# HDMIspartan6_Rev_A_brd.net
KiCad netlist of a schematic drawn in EAGLE
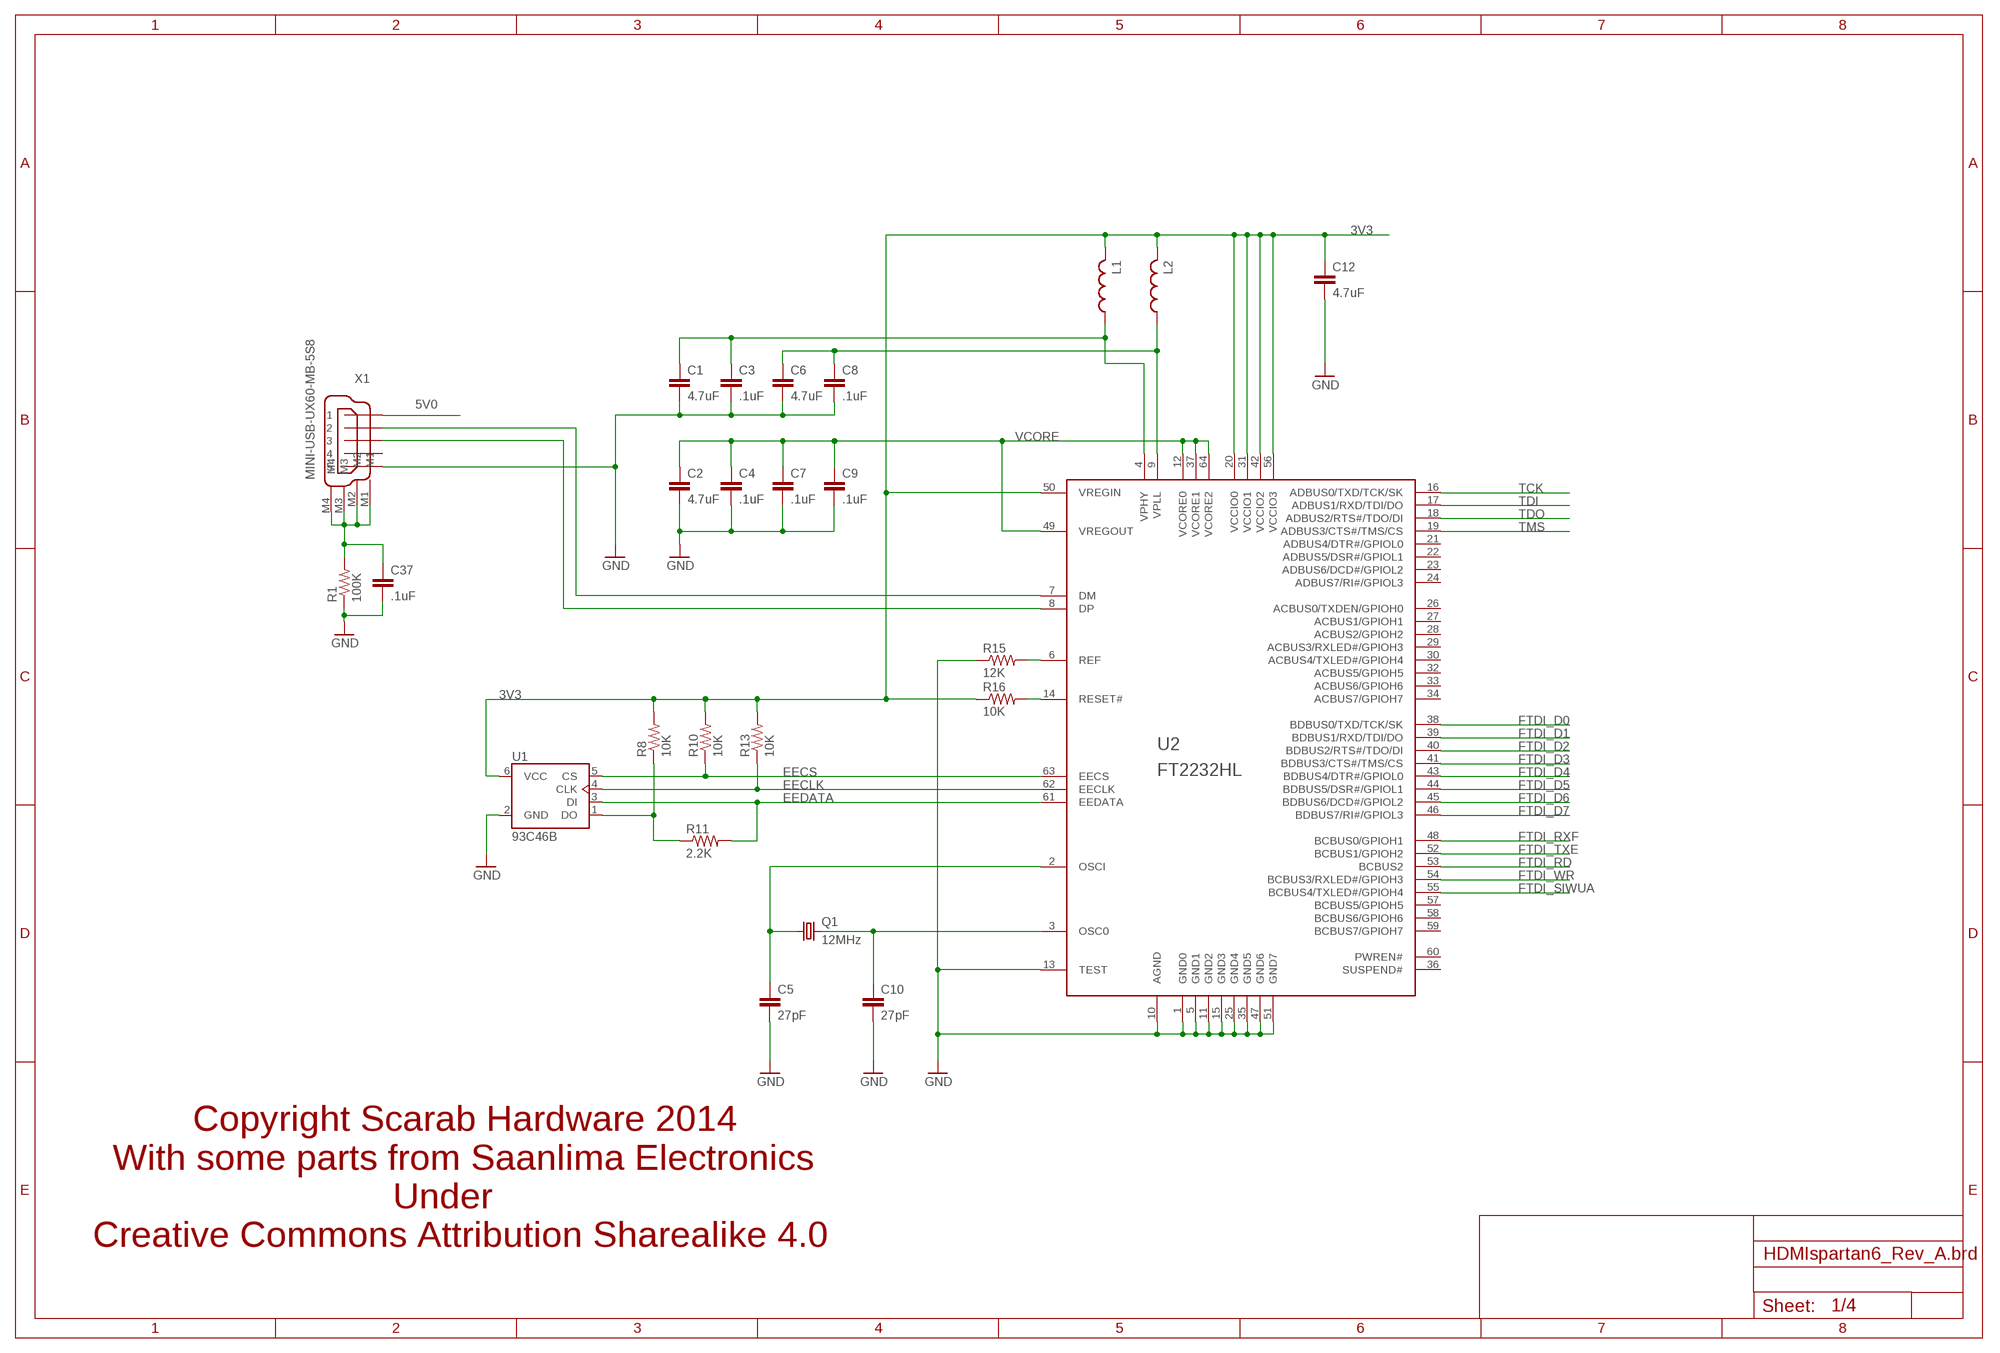
[diagram p0: schematic, sheet 1]
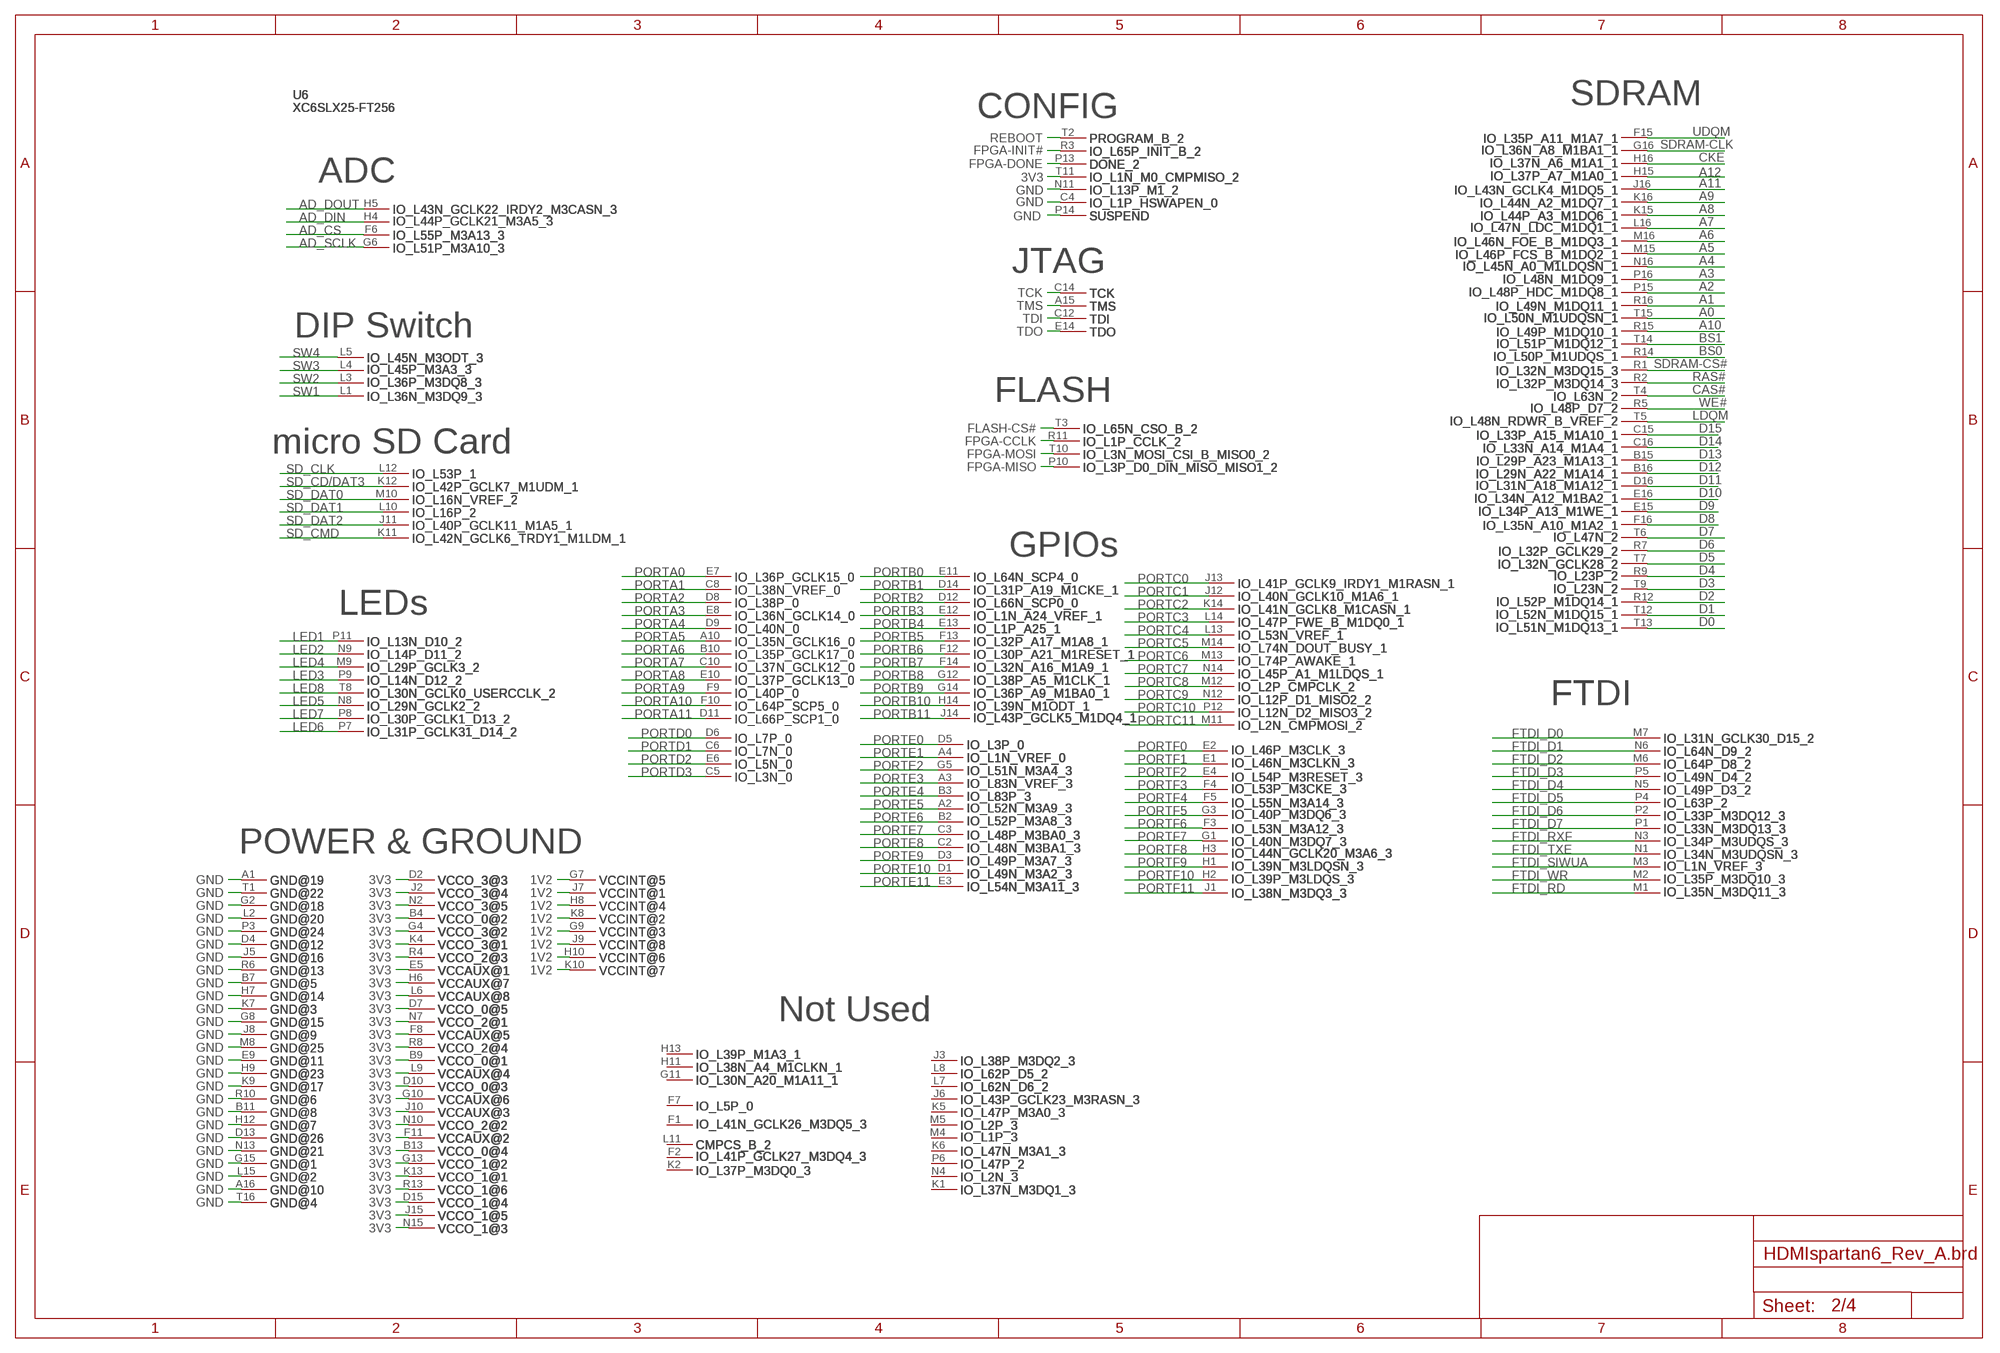
[diagram p1: schematic, sheet 2]
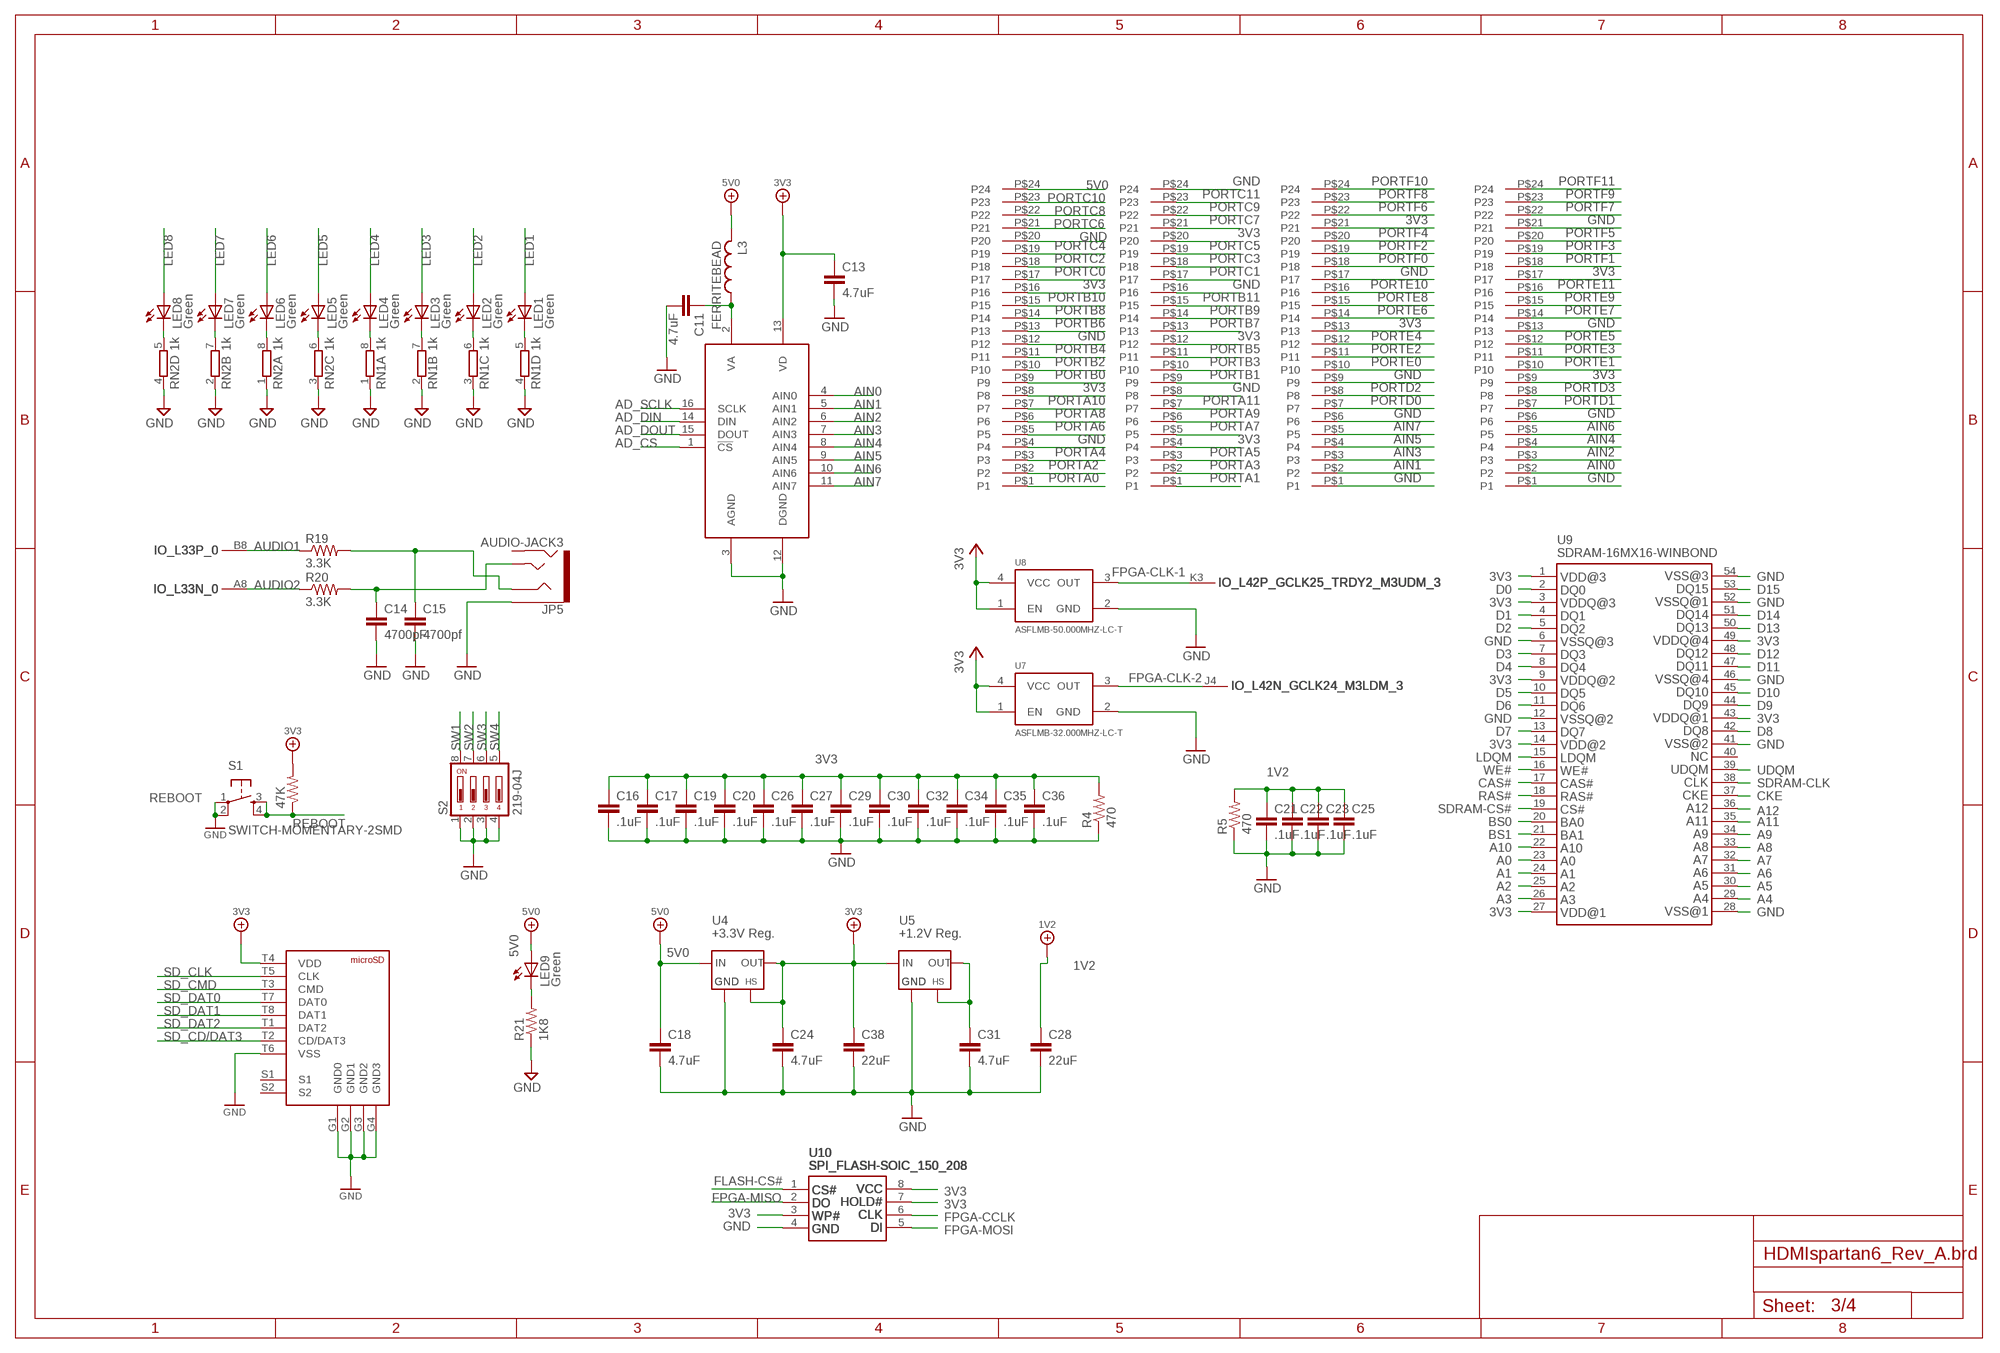
[diagram p2: schematic, sheet 3]
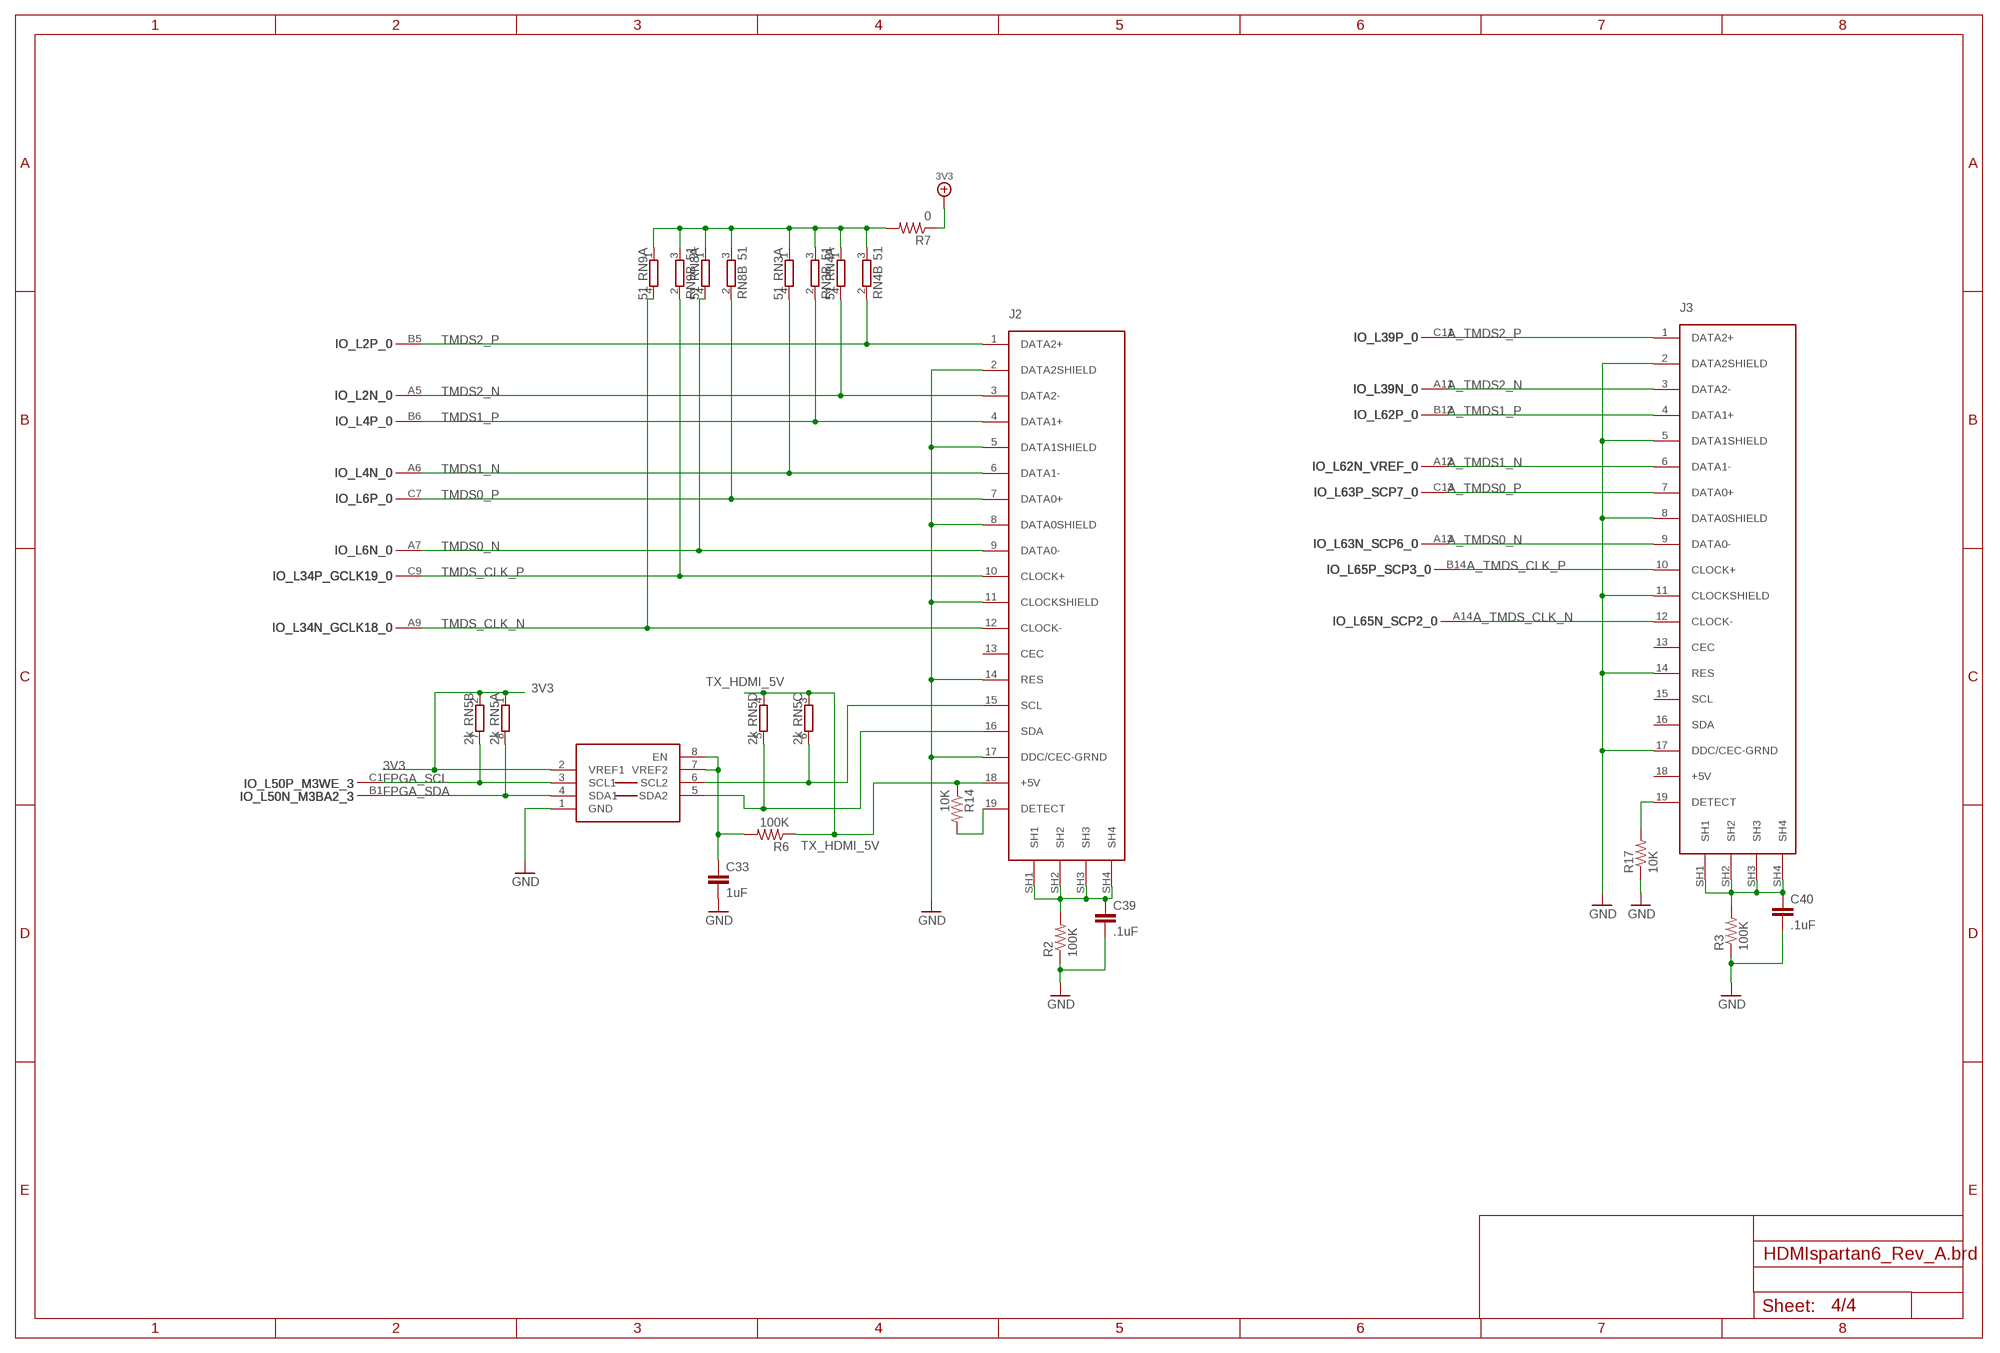
[diagram p3: schematic, sheet 4]

(export (version "E")
  (design (tool "Eeschema 10.0.6"))
  (components
    (comp (ref "U6")
      (value "XC6SLX25-FT256")
      (footprint "eagle-import:XILINX-FT256")
      (fields
        (field (name "DIGIKEY#") "122-1753-ND")
        (field (name "MANF") "XILINX")
        (field (name "MANF#") "XC6SLX25-2FTG256C")
      )
      (libsource (lib "eagle-import") (part "XC6SLX25-FT256"))
    )
    (comp (ref "C11")
      (value "4.7uF")
      (footprint "eagle-import:C0603K")
      (libsource (lib "eagle-import") (part "C-EUC0603K"))
    )
    (comp (ref "C13")
      (value "4.7uF")
      (footprint "eagle-import:C0603K")
      (libsource (lib "eagle-import") (part "C-EUC0603K"))
    )
    (comp (ref "C14")
      (value "4700pF")
      (footprint "eagle-import:C0603K")
      (libsource (lib "eagle-import") (part "C-EUC0603K"))
    )
    (comp (ref "C15")
      (value "4700pf")
      (footprint "eagle-import:C0603K")
      (libsource (lib "eagle-import") (part "C-EUC0603K"))
    )
    (comp (ref "C16")
      (value ".1uF")
      (footprint "eagle-import:C0603K")
      (libsource (lib "eagle-import") (part "C-EUC0603K"))
    )
    (comp (ref "C17")
      (value ".1uF")
      (footprint "eagle-import:C0603K")
      (libsource (lib "eagle-import") (part "C-EUC0603K"))
    )
    (comp (ref "C18")
      (value "4.7uF")
      (footprint "eagle-import:C0603K")
      (fields (field (name "MANF") "Murata"))
      (libsource (lib "eagle-import") (part "C-EUC0603K"))
    )
    (comp (ref "C19")
      (value ".1uF")
      (footprint "eagle-import:C0603K")
      (libsource (lib "eagle-import") (part "C-EUC0603K"))
    )
    (comp (ref "C20")
      (value ".1uF")
      (footprint "eagle-import:C0603K")
      (libsource (lib "eagle-import") (part "C-EUC0603K"))
    )
    (comp (ref "C21")
      (value ".1uF")
      (footprint "eagle-import:C0603K")
      (libsource (lib "eagle-import") (part "C-EUC0603K"))
    )
    (comp (ref "C22")
      (value ".1uF")
      (footprint "eagle-import:C0603K")
      (libsource (lib "eagle-import") (part "C-EUC0603K"))
    )
    (comp (ref "C23")
      (value ".1uF")
      (footprint "eagle-import:C0603K")
      (libsource (lib "eagle-import") (part "C-EUC0603K"))
    )
    (comp (ref "C24")
      (value "4.7uF")
      (footprint "eagle-import:C0603K")
      (fields (field (name "MANF") "Murata"))
      (libsource (lib "eagle-import") (part "C-EUC0603K"))
    )
    (comp (ref "C25")
      (value ".1uF")
      (footprint "eagle-import:C0603K")
      (libsource (lib "eagle-import") (part "C-EUC0603K"))
    )
    (comp (ref "C26")
      (value ".1uF")
      (footprint "eagle-import:C0603K")
      (libsource (lib "eagle-import") (part "C-EUC0603K"))
    )
    (comp (ref "C27")
      (value ".1uF")
      (footprint "eagle-import:C0603K")
      (libsource (lib "eagle-import") (part "C-EUC0603K"))
    )
    (comp (ref "C28")
      (value "22uF")
      (footprint "eagle-import:C0603K")
      (fields (field (name "MANF") "Murata"))
      (libsource (lib "eagle-import") (part "C-EUC0603K"))
    )
    (comp (ref "C29")
      (value ".1uF")
      (footprint "eagle-import:C0603K")
      (libsource (lib "eagle-import") (part "C-EUC0603K"))
    )
    (comp (ref "C30")
      (value ".1uF")
      (footprint "eagle-import:C0603K")
      (libsource (lib "eagle-import") (part "C-EUC0603K"))
    )
    (comp (ref "C31")
      (value "4.7uF")
      (footprint "eagle-import:C0603K")
      (fields (field (name "MANF") "Murata"))
      (libsource (lib "eagle-import") (part "C-EUC0603K"))
    )
    (comp (ref "C32")
      (value ".1uF")
      (footprint "eagle-import:C0603K")
      (libsource (lib "eagle-import") (part "C-EUC0603K"))
    )
    (comp (ref "C34")
      (value ".1uF")
      (footprint "eagle-import:C0603K")
      (libsource (lib "eagle-import") (part "C-EUC0603K"))
    )
    (comp (ref "C35")
      (value ".1uF")
      (footprint "eagle-import:C0603K")
      (libsource (lib "eagle-import") (part "C-EUC0603K"))
    )
    (comp (ref "C36")
      (value ".1uF")
      (footprint "eagle-import:C0603K")
      (libsource (lib "eagle-import") (part "C-EUC0603K"))
    )
    (comp (ref "C38")
      (value "22uF")
      (footprint "eagle-import:C0603K")
      (fields (field (name "MANF") "Murata"))
      (libsource (lib "eagle-import") (part "C-EUC0603K"))
    )
    (comp (ref "J4")
      (value "P24-1")
      (footprint "eagle-import:1X24")
      (libsource (lib "eagle-import") (part "P24-1"))
    )
    (comp (ref "J5")
      (value "MICROSD_MOLEX")
      (footprint "eagle-import:MICROSD_104031")
      (libsource (lib "eagle-import") (part "MICROSD_MOLEX"))
    )
    (comp (ref "J6")
      (value "P24-1")
      (footprint "eagle-import:1X24")
      (libsource (lib "eagle-import") (part "P24-1"))
    )
    (comp (ref "JP5")
      (value "AUDIO-JACK3")
      (footprint "eagle-import:AUDIO-JACK-TRRS-SMD")
      (libsource (lib "eagle-import") (part "AUDIO-JACK3"))
    )
    (comp (ref "L3")
      (value "FERRITEBEAD")
      (footprint "eagle-import:L2012C")
      (libsource (lib "eagle-import") (part "L-USL2012C"))
    )
    (comp (ref "LED1")
      (value "Green")
      (footprint "eagle-import:SML0603")
      (libsource (lib "eagle-import") (part "LEDSML0603"))
    )
    (comp (ref "LED2")
      (value "Green")
      (footprint "eagle-import:SML0603")
      (libsource (lib "eagle-import") (part "LEDSML0603"))
    )
    (comp (ref "LED3")
      (value "Green")
      (footprint "eagle-import:SML0603")
      (libsource (lib "eagle-import") (part "LEDSML0603"))
    )
    (comp (ref "LED4")
      (value "Green")
      (footprint "eagle-import:SML0603")
      (libsource (lib "eagle-import") (part "LEDSML0603"))
    )
    (comp (ref "LED5")
      (value "Green")
      (footprint "eagle-import:SML0603")
      (libsource (lib "eagle-import") (part "LEDSML0603"))
    )
    (comp (ref "LED6")
      (value "Green")
      (footprint "eagle-import:SML0603")
      (libsource (lib "eagle-import") (part "LEDSML0603"))
    )
    (comp (ref "LED7")
      (value "Green")
      (footprint "eagle-import:SML0603")
      (libsource (lib "eagle-import") (part "LEDSML0603"))
    )
    (comp (ref "LED8")
      (value "Green")
      (footprint "eagle-import:SML0603")
      (libsource (lib "eagle-import") (part "LEDSML0603"))
    )
    (comp (ref "LED9")
      (value "Green")
      (footprint "eagle-import:SML0603")
      (libsource (lib "eagle-import") (part "LEDSML0603"))
    )
    (comp (ref "R4")
      (value "470")
      (footprint "eagle-import:R0603")
      (libsource (lib "eagle-import") (part "R-US_R0603"))
    )
    (comp (ref "R5")
      (value "470")
      (footprint "eagle-import:R0603")
      (libsource (lib "eagle-import") (part "R-US_R0603"))
    )
    (comp (ref "R18")
      (value "47K")
      (footprint "eagle-import:R0603")
      (libsource (lib "eagle-import") (part "R-US_R0603"))
    )
    (comp (ref "R19")
      (value "3.3K")
      (footprint "eagle-import:R0603")
      (libsource (lib "eagle-import") (part "R-US_R0603"))
    )
    (comp (ref "R20")
      (value "3.3K")
      (footprint "eagle-import:R0603")
      (libsource (lib "eagle-import") (part "R-US_R0603"))
    )
    (comp (ref "R21")
      (value "1K8")
      (footprint "eagle-import:R0603")
      (libsource (lib "eagle-import") (part "R-US_R0603"))
    )
    (comp (ref "RN1")
      (value "1k")
      (footprint "eagle-import:0603-ARV")
      (libsource (lib "eagle-import") (part "4R-N0603-ARV"))
    )
    (comp (ref "RN2")
      (value "1k")
      (footprint "eagle-import:0603-ARV")
      (libsource (lib "eagle-import") (part "4R-N0603-ARV"))
    )
    (comp (ref "S1")
      (value "SWITCH-MOMENTARY-2SMD")
      (footprint "eagle-import:TACTILE_SWITCH_SMD")
      (libsource (lib "eagle-import") (part "TAC_SWITCHSMD"))
    )
    (comp (ref "S2")
      (value "219-04J")
      (footprint "eagle-import:CTS-219-04J")
      (libsource (lib "eagle-import") (part "219-04J"))
    )
    (comp (ref "U$7")
      (value "P24-1")
      (footprint "eagle-import:1X24")
      (libsource (lib "eagle-import") (part "P24-1"))
    )
    (comp (ref "U$8")
      (value "P24-1")
      (footprint "eagle-import:1X24")
      (libsource (lib "eagle-import") (part "P24-1"))
    )
    (comp (ref "U3")
      (value "ADC088S102CIMT")
      (footprint "eagle-import:TSSOP16")
      (libsource (lib "eagle-import") (part "ADC088S102CIMT"))
    )
    (comp (ref "U4")
      (value "+3.3V Reg.")
      (footprint "eagle-import:SOT223")
      (fields (field (name "MANF") "Diodes/Zetex"))
      (libsource (lib "eagle-import") (part "FAN1117"))
    )
    (comp (ref "U5")
      (value "+1.2V Reg.")
      (footprint "eagle-import:SOT223")
      (fields (field (name "MANF") "Diodes/Zetex"))
      (libsource (lib "eagle-import") (part "FAN1112"))
    )
    (comp (ref "U7")
      (value "ASFLMB-32.000MHZ-LC-T")
      (footprint "eagle-import:CRYSTAL-OSC-SMD-5X3")
      (libsource (lib "eagle-import") (part "OSCILLATOR5X3-PIN1-INDICATED"))
    )
    (comp (ref "U8")
      (value "ASFLMB-50.000MHZ-LC-T")
      (footprint "eagle-import:CRYSTAL-OSC-SMD-5X3")
      (libsource (lib "eagle-import") (part "OSCILLATOR5X3-PIN1-INDICATED"))
    )
    (comp (ref "U9")
      (value "SDRAM-16MX16-WINBOND")
      (footprint "eagle-import:TSOPII-54")
      (fields (field (name "MANF") "Winbond"))
      (libsource (lib "eagle-import") (part "SDRAM-16MX16-WINBOND"))
    )
    (comp (ref "U10")
      (value "SPI_FLASH-SOIC_150_208")
      (footprint "eagle-import:SPI-8_SOIC_150_208")
      (fields
        (field (name "MANF") "Winbond")
        (field (name "DIGIKEY#") "W25Q80BVSNIG-ND")
        (field (name "MANF_1") "Winbond")
        (field (name "MANF#") "W25Q80BVSNIG")
      )
      (libsource (lib "eagle-import") (part "SPI_FLASH-SOIC_150_208"))
    )
    (comp (ref "C33")
      (value "1uF")
      (footprint "eagle-import:C0603K")
      (libsource (lib "eagle-import") (part "C-EUC0603K"))
    )
    (comp (ref "C39")
      (value ".1uF")
      (footprint "eagle-import:C0603K")
      (libsource (lib "eagle-import") (part "C-EUC0603K"))
    )
    (comp (ref "C40")
      (value ".1uF")
      (footprint "eagle-import:C0603K")
      (libsource (lib "eagle-import") (part "C-EUC0603K"))
    )
    (comp (ref "J2")
      (value "HDMI-TYPE-A-RECEPTICALFCI10029449")
      (footprint "eagle-import:FCI-HDMI-TYPE-A-RECEPT")
      (libsource (lib "eagle-import") (part "HDMI-TYPE-A-RECEPTICALFCI10029449"))
    )
    (comp (ref "J3")
      (value "HDMI-TYPE-A-RECEPTICALFCI10029449")
      (footprint "eagle-import:FCI-HDMI-TYPE-A-RECEPT")
      (libsource (lib "eagle-import") (part "HDMI-TYPE-A-RECEPTICALFCI10029449"))
    )
    (comp (ref "R2")
      (value "100K")
      (footprint "eagle-import:R0603")
      (libsource (lib "eagle-import") (part "R-US_R0603"))
    )
    (comp (ref "R3")
      (value "100K")
      (footprint "eagle-import:R0603")
      (libsource (lib "eagle-import") (part "R-US_R0603"))
    )
    (comp (ref "R6")
      (value "100K")
      (footprint "eagle-import:R0603")
      (libsource (lib "eagle-import") (part "R-US_R0603"))
    )
    (comp (ref "R7")
      (value "0")
      (footprint "eagle-import:R0603")
      (libsource (lib "eagle-import") (part "R-US_R0603"))
    )
    (comp (ref "R14")
      (value "10K")
      (footprint "eagle-import:R0603")
      (libsource (lib "eagle-import") (part "R-US_R0603"))
    )
    (comp (ref "R17")
      (value "10K")
      (footprint "eagle-import:R0603")
      (libsource (lib "eagle-import") (part "R-US_R0603"))
    )
    (comp (ref "RN3")
      (value "51")
      (footprint "eagle-import:EXB34V")
      (libsource (lib "eagle-import") (part "2R-NEXB34V"))
    )
    (comp (ref "RN4")
      (value "51")
      (footprint "eagle-import:EXB34V")
      (libsource (lib "eagle-import") (part "2R-NEXB34V"))
    )
    (comp (ref "RN5")
      (value "2k")
      (footprint "eagle-import:0603-ARV")
      (libsource (lib "eagle-import") (part "4R-N0603-ARV"))
    )
    (comp (ref "RN8")
      (value "51")
      (footprint "eagle-import:EXB34V")
      (libsource (lib "eagle-import") (part "2R-NEXB34V"))
    )
    (comp (ref "RN9")
      (value "51")
      (footprint "eagle-import:EXB34V")
      (libsource (lib "eagle-import") (part "2R-NEXB34V"))
    )
    (comp (ref "U11")
      (value "PCA9306")
      (footprint "eagle-import:PSOP-8")
      (libsource (lib "eagle-import") (part "PCA9306"))
    )
    (comp (ref "C1")
      (value "4.7uF")
      (footprint "eagle-import:C0603K")
      (libsource (lib "eagle-import") (part "C-EUC0603K"))
    )
    (comp (ref "C2")
      (value "4.7uF")
      (footprint "eagle-import:C0603K")
      (libsource (lib "eagle-import") (part "C-EUC0603K"))
    )
    (comp (ref "C3")
      (value ".1uF")
      (footprint "eagle-import:C0603K")
      (libsource (lib "eagle-import") (part "C-EUC0603K"))
    )
    (comp (ref "C4")
      (value ".1uF")
      (footprint "eagle-import:C0603K")
      (libsource (lib "eagle-import") (part "C-EUC0603K"))
    )
    (comp (ref "C5")
      (value "27pF")
      (footprint "eagle-import:C0603K")
      (libsource (lib "eagle-import") (part "C-EUC0603K"))
    )
    (comp (ref "C6")
      (value "4.7uF")
      (footprint "eagle-import:C0603K")
      (libsource (lib "eagle-import") (part "C-EUC0603K"))
    )
    (comp (ref "C7")
      (value ".1uF")
      (footprint "eagle-import:C0603K")
      (libsource (lib "eagle-import") (part "C-EUC0603K"))
    )
    (comp (ref "C8")
      (value ".1uF")
      (footprint "eagle-import:C0603K")
      (libsource (lib "eagle-import") (part "C-EUC0603K"))
    )
    (comp (ref "C9")
      (value ".1uF")
      (footprint "eagle-import:C0603K")
      (libsource (lib "eagle-import") (part "C-EUC0603K"))
    )
    (comp (ref "C10")
      (value "27pF")
      (footprint "eagle-import:C0603K")
      (libsource (lib "eagle-import") (part "C-EUC0603K"))
    )
    (comp (ref "C12")
      (value "4.7uF")
      (footprint "eagle-import:C0603K")
      (libsource (lib "eagle-import") (part "C-EUC0603K"))
    )
    (comp (ref "C37")
      (value ".1uF")
      (footprint "eagle-import:C0603K")
      (libsource (lib "eagle-import") (part "C-EUC0603K"))
    )
    (comp (ref "L1")
      (value "L-USL2012C")
      (footprint "eagle-import:L2012C")
      (libsource (lib "eagle-import") (part "L-USL2012C"))
    )
    (comp (ref "L2")
      (value "L-USL2012C")
      (footprint "eagle-import:L2012C")
      (libsource (lib "eagle-import") (part "L-USL2012C"))
    )
    (comp (ref "Q1")
      (value "12MHz")
      (footprint "eagle-import:CRYSTAL3.2X2.5MM")
      (libsource (lib "eagle-import") (part "CRYSTAL3.2X2.5"))
    )
    (comp (ref "R1")
      (value "100K")
      (footprint "eagle-import:R0603")
      (libsource (lib "eagle-import") (part "R-US_R0603"))
    )
    (comp (ref "R8")
      (value "10K")
      (footprint "eagle-import:R0603")
      (libsource (lib "eagle-import") (part "R-US_R0603"))
    )
    (comp (ref "R10")
      (value "10K")
      (footprint "eagle-import:R0603")
      (libsource (lib "eagle-import") (part "R-US_R0603"))
    )
    (comp (ref "R11")
      (value "2.2K")
      (footprint "eagle-import:R0603")
      (libsource (lib "eagle-import") (part "R-US_R0603"))
    )
    (comp (ref "R13")
      (value "10K")
      (footprint "eagle-import:R0603")
      (libsource (lib "eagle-import") (part "R-US_R0603"))
    )
    (comp (ref "R15")
      (value "12K")
      (footprint "eagle-import:R0603")
      (libsource (lib "eagle-import") (part "R-US_R0603"))
    )
    (comp (ref "R16")
      (value "10K")
      (footprint "eagle-import:R0603")
      (libsource (lib "eagle-import") (part "R-US_R0603"))
    )
    (comp (ref "U1")
      (value "93C46B")
      (footprint "eagle-import:SOT23-6")
      (libsource (lib "eagle-import") (part "DIGITAL-EEPROM-MICROWIRE-6P_SOT23"))
    )
    (comp (ref "U2")
      (value "FT2232HL")
      (footprint "eagle-import:LQFP64")
      (libsource (lib "eagle-import") (part "FT2232H"))
    )
    (comp (ref "X1")
      (value "MINI-USB-UX60-MB-5S8")
      (footprint "eagle-import:UX60-MB-5S8")
      (libsource (lib "eagle-import") (part "MINI-USB-UX60-MB-5S8"))
    )
  )
  (nets
    (net (code "1") (name "1V2") (class "Default")
      (node (ref "C21") (pin "1") (pinfunction "1_1") (pintype "passive"))
      (node (ref "C22") (pin "1") (pinfunction "1_1") (pintype "passive"))
      (node (ref "C23") (pin "1") (pinfunction "1_1") (pintype "passive"))
      (node (ref "C25") (pin "1") (pinfunction "1_1") (pintype "passive"))
      (node (ref "C28") (pin "1") (pinfunction "1_1") (pintype "passive"))
      (node (ref "R5") (pin "2") (pinfunction "2_2") (pintype "passive"))
      (node (ref "U6") (pin "G7") (pinfunction "1_G7") (pintype "input"))
      (node (ref "U6") (pin "G9") (pinfunction "1_G9") (pintype "input"))
      (node (ref "U6") (pin "H10") (pinfunction "1_H10") (pintype "input"))
      (node (ref "U6") (pin "H8") (pinfunction "1_H8") (pintype "input"))
      (node (ref "U6") (pin "J7") (pinfunction "1_J7") (pintype "input"))
      (node (ref "U6") (pin "J9") (pinfunction "1_J9") (pintype "input"))
      (node (ref "U6") (pin "K10") (pinfunction "1_K10") (pintype "input"))
      (node (ref "U6") (pin "K8") (pinfunction "1_K8") (pintype "input"))
    )
    (net (code "2") (name "3V3") (class "Default")
      (node (ref "C12") (pin "1") (pinfunction "1_1") (pintype "passive"))
      (node (ref "C13") (pin "1") (pinfunction "1_1") (pintype "passive"))
      (node (ref "C16") (pin "1") (pinfunction "1_1") (pintype "passive"))
      (node (ref "C17") (pin "1") (pinfunction "1_1") (pintype "passive"))
      (node (ref "C19") (pin "1") (pinfunction "1_1") (pintype "passive"))
      (node (ref "C20") (pin "1") (pinfunction "1_1") (pintype "passive"))
      (node (ref "C24") (pin "1") (pinfunction "1_1") (pintype "passive"))
      (node (ref "C26") (pin "1") (pinfunction "1_1") (pintype "passive"))
      (node (ref "C27") (pin "1") (pinfunction "1_1") (pintype "passive"))
      (node (ref "C29") (pin "1") (pinfunction "1_1") (pintype "passive"))
      (node (ref "C30") (pin "1") (pinfunction "1_1") (pintype "passive"))
      (node (ref "C32") (pin "1") (pinfunction "1_1") (pintype "passive"))
      (node (ref "C34") (pin "1") (pinfunction "1_1") (pintype "passive"))
      (node (ref "C35") (pin "1") (pinfunction "1_1") (pintype "passive"))
      (node (ref "C36") (pin "1") (pinfunction "1_1") (pintype "passive"))
      (node (ref "C38") (pin "1") (pinfunction "1_1") (pintype "passive"))
      (node (ref "J4") (pin "P$13") (pinfunction "P13_P$13") (pintype "bidirectional"))
      (node (ref "J4") (pin "P$21") (pinfunction "P21_P$21") (pintype "bidirectional"))
      (node (ref "J5") (pin "T4") (pinfunction "VDD_T4") (pintype "bidirectional"))
      (node (ref "J6") (pin "P$17") (pinfunction "P17_P$17") (pintype "bidirectional"))
      (node (ref "J6") (pin "P$9") (pinfunction "P9_P$9") (pintype "bidirectional"))
      (node (ref "L1") (pin "2") (pinfunction "2_2") (pintype "passive"))
      (node (ref "L2") (pin "2") (pinfunction "2_2") (pintype "passive"))
      (node (ref "R10") (pin "2") (pinfunction "2_2") (pintype "passive"))
      (node (ref "R13") (pin "2") (pinfunction "2_2") (pintype "passive"))
      (node (ref "R16") (pin "1") (pinfunction "1_1") (pintype "passive"))
      (node (ref "R18") (pin "2") (pinfunction "2_2") (pintype "passive"))
      (node (ref "R4") (pin "2") (pinfunction "2_2") (pintype "passive"))
      (node (ref "R7") (pin "1") (pinfunction "1_1") (pintype "passive"))
      (node (ref "R8") (pin "2") (pinfunction "2_2") (pintype "passive"))
      (node (ref "RN5") (pin "1") (pinfunction "1_1") (pintype "passive"))
      (node (ref "RN5") (pin "2") (pinfunction "1_2") (pintype "passive"))
      (node (ref "U$7") (pin "P$16") (pinfunction "P16_P$16") (pintype "bidirectional"))
      (node (ref "U$7") (pin "P$8") (pinfunction "P8_P$8") (pintype "bidirectional"))
      (node (ref "U$8") (pin "P$12") (pinfunction "P12_P$12") (pintype "bidirectional"))
      (node (ref "U$8") (pin "P$20") (pinfunction "P20_P$20") (pintype "bidirectional"))
      (node (ref "U$8") (pin "P$4") (pinfunction "P4_P$4") (pintype "bidirectional"))
      (node (ref "U1") (pin "6") (pinfunction "VCC_6") (pintype "input"))
      (node (ref "U10") (pin "3") (pinfunction "1_3") (pintype "input"))
      (node (ref "U10") (pin "7") (pinfunction "1_7") (pintype "input"))
      (node (ref "U10") (pin "8") (pinfunction "1_8") (pintype "input"))
      (node (ref "U11") (pin "2") (pinfunction "VREF1_2") (pintype "bidirectional"))
      (node (ref "U2") (pin "20") (pinfunction "VCCIO0_20") (pintype "bidirectional"))
      (node (ref "U2") (pin "31") (pinfunction "VCCIO1_31") (pintype "bidirectional"))
      (node (ref "U2") (pin "42") (pinfunction "VCCIO2_42") (pintype "bidirectional"))
      (node (ref "U2") (pin "50") (pinfunction "VREGIN_50") (pintype "bidirectional"))
      (node (ref "U2") (pin "56") (pinfunction "VCCIO3_56") (pintype "bidirectional"))
      (node (ref "U3") (pin "13") (pinfunction "VD_13") (pintype "power_in"))
      (node (ref "U4") (pin "2") (pinfunction "OUT_2") (pintype "passive"))
      (node (ref "U4") (pin "4") (pinfunction "HS_4") (pintype "passive"))
      (node (ref "U5") (pin "3") (pinfunction "IN_3") (pintype "input"))
      (node (ref "U6") (pin "B13") (pinfunction "1_B13") (pintype "input"))
      (node (ref "U6") (pin "B4") (pinfunction "1_B4") (pintype "input"))
      (node (ref "U6") (pin "B9") (pinfunction "1_B9") (pintype "input"))
      (node (ref "U6") (pin "D10") (pinfunction "1_D10") (pintype "input"))
      (node (ref "U6") (pin "D15") (pinfunction "1_D15") (pintype "input"))
      (node (ref "U6") (pin "D2") (pinfunction "1_D2") (pintype "input"))
      (node (ref "U6") (pin "D7") (pinfunction "1_D7") (pintype "input"))
      (node (ref "U6") (pin "E5") (pinfunction "1_E5") (pintype "input"))
      (node (ref "U6") (pin "F11") (pinfunction "1_F11") (pintype "input"))
      (node (ref "U6") (pin "F8") (pinfunction "1_F8") (pintype "input"))
      (node (ref "U6") (pin "G10") (pinfunction "1_G10") (pintype "input"))
      (node (ref "U6") (pin "G13") (pinfunction "1_G13") (pintype "input"))
      (node (ref "U6") (pin "G4") (pinfunction "1_G4") (pintype "input"))
      (node (ref "U6") (pin "H6") (pinfunction "1_H6") (pintype "input"))
      (node (ref "U6") (pin "J10") (pinfunction "1_J10") (pintype "input"))
      (node (ref "U6") (pin "J15") (pinfunction "1_J15") (pintype "input"))
      (node (ref "U6") (pin "J2") (pinfunction "1_J2") (pintype "input"))
      (node (ref "U6") (pin "K13") (pinfunction "1_K13") (pintype "input"))
      (node (ref "U6") (pin "K4") (pinfunction "1_K4") (pintype "input"))
      (node (ref "U6") (pin "L6") (pinfunction "1_L6") (pintype "input"))
      (node (ref "U6") (pin "L9") (pinfunction "1_L9") (pintype "input"))
      (node (ref "U6") (pin "N10") (pinfunction "1_N10") (pintype "input"))
      (node (ref "U6") (pin "N15") (pinfunction "1_N15") (pintype "input"))
      (node (ref "U6") (pin "N2") (pinfunction "1_N2") (pintype "input"))
      (node (ref "U6") (pin "N7") (pinfunction "1_N7") (pintype "input"))
      (node (ref "U6") (pin "R13") (pinfunction "1_R13") (pintype "input"))
      (node (ref "U6") (pin "R4") (pinfunction "1_R4") (pintype "input"))
      (node (ref "U6") (pin "R8") (pinfunction "1_R8") (pintype "input"))
      (node (ref "U6") (pin "T11") (pinfunction "1_T11") (pintype "bidirectional"))
      (node (ref "U7") (pin "1") (pinfunction "EN_1") (pintype "bidirectional"))
      (node (ref "U7") (pin "4") (pinfunction "VCC_4") (pintype "bidirectional"))
      (node (ref "U8") (pin "1") (pinfunction "EN_1") (pintype "bidirectional"))
      (node (ref "U8") (pin "4") (pinfunction "VCC_4") (pintype "bidirectional"))
      (node (ref "U9") (pin "1") (pinfunction "P$1_1") (pintype "bidirectional"))
      (node (ref "U9") (pin "14") (pinfunction "P$1_14") (pintype "bidirectional"))
      (node (ref "U9") (pin "27") (pinfunction "P$1_27") (pintype "bidirectional"))
      (node (ref "U9") (pin "3") (pinfunction "P$1_3") (pintype "bidirectional"))
      (node (ref "U9") (pin "43") (pinfunction "P$1_43") (pintype "bidirectional"))
      (node (ref "U9") (pin "49") (pinfunction "P$1_49") (pintype "bidirectional"))
      (node (ref "U9") (pin "9") (pinfunction "P$1_9") (pintype "bidirectional"))
    )
    (net (code "3") (name "5V0") (class "Default")
      (node (ref "C18") (pin "1") (pinfunction "1_1") (pintype "passive"))
      (node (ref "L3") (pin "2") (pinfunction "2_2") (pintype "passive"))
      (node (ref "LED9") (pin "A") (pinfunction "A_A") (pintype "passive"))
      (node (ref "U$7") (pin "P$24") (pinfunction "P24_P$24") (pintype "bidirectional"))
      (node (ref "U4") (pin "3") (pinfunction "IN_3") (pintype "input"))
      (node (ref "X1") (pin "1") (pinfunction "1_1") (pintype "input"))
    )
    (net (code "4") (name "A0") (class "Default")
      (node (ref "U6") (pin "T15") (pinfunction "1_T15") (pintype "bidirectional"))
      (node (ref "U9") (pin "23") (pinfunction "P$1_23") (pintype "bidirectional"))
    )
    (net (code "5") (name "A1") (class "Default")
      (node (ref "U6") (pin "R16") (pinfunction "1_R16") (pintype "bidirectional"))
      (node (ref "U9") (pin "24") (pinfunction "P$1_24") (pintype "bidirectional"))
    )
    (net (code "6") (name "A2") (class "Default")
      (node (ref "U6") (pin "P15") (pinfunction "1_P15") (pintype "bidirectional"))
      (node (ref "U9") (pin "25") (pinfunction "P$1_25") (pintype "bidirectional"))
    )
    (net (code "7") (name "A3") (class "Default")
      (node (ref "U6") (pin "P16") (pinfunction "1_P16") (pintype "bidirectional"))
      (node (ref "U9") (pin "26") (pinfunction "P$1_26") (pintype "bidirectional"))
    )
    (net (code "8") (name "A4") (class "Default")
      (node (ref "U6") (pin "N16") (pinfunction "1_N16") (pintype "bidirectional"))
      (node (ref "U9") (pin "29") (pinfunction "P$1_29") (pintype "bidirectional"))
    )
    (net (code "9") (name "A5") (class "Default")
      (node (ref "U6") (pin "M15") (pinfunction "1_M15") (pintype "bidirectional"))
      (node (ref "U9") (pin "30") (pinfunction "P$1_30") (pintype "bidirectional"))
    )
    (net (code "10") (name "A6") (class "Default")
      (node (ref "U6") (pin "M16") (pinfunction "1_M16") (pintype "bidirectional"))
      (node (ref "U9") (pin "31") (pinfunction "P$1_31") (pintype "bidirectional"))
    )
    (net (code "11") (name "A7") (class "Default")
      (node (ref "U6") (pin "L16") (pinfunction "1_L16") (pintype "bidirectional"))
      (node (ref "U9") (pin "32") (pinfunction "P$1_32") (pintype "bidirectional"))
    )
    (net (code "12") (name "A8") (class "Default")
      (node (ref "U6") (pin "K15") (pinfunction "1_K15") (pintype "bidirectional"))
      (node (ref "U9") (pin "33") (pinfunction "P$1_33") (pintype "bidirectional"))
    )
    (net (code "13") (name "A9") (class "Default")
      (node (ref "U6") (pin "K16") (pinfunction "1_K16") (pintype "bidirectional"))
      (node (ref "U9") (pin "34") (pinfunction "P$1_34") (pintype "bidirectional"))
    )
    (net (code "14") (name "A10") (class "Default")
      (node (ref "U6") (pin "R15") (pinfunction "1_R15") (pintype "bidirectional"))
      (node (ref "U9") (pin "22") (pinfunction "P$1_22") (pintype "bidirectional"))
    )
    (net (code "15") (name "A11") (class "Default")
      (node (ref "U6") (pin "J16") (pinfunction "1_J16") (pintype "bidirectional"))
      (node (ref "U9") (pin "35") (pinfunction "P$1_35") (pintype "bidirectional"))
    )
    (net (code "16") (name "A12") (class "Default")
      (node (ref "U6") (pin "H15") (pinfunction "1_H15") (pintype "bidirectional"))
      (node (ref "U9") (pin "36") (pinfunction "P$1_36") (pintype "bidirectional"))
    )
    (net (code "17") (name "AD_CS") (class "Default")
      (node (ref "U3") (pin "1") (pinfunction "~{CS}_1") (pintype "input"))
      (node (ref "U6") (pin "F6") (pinfunction "1_F6") (pintype "bidirectional"))
    )
    (net (code "18") (name "AD_DIN") (class "Default")
      (node (ref "U3") (pin "14") (pinfunction "DIN_14") (pintype "input"))
      (node (ref "U6") (pin "H4") (pinfunction "1_H4") (pintype "bidirectional"))
    )
    (net (code "19") (name "AD_DOUT") (class "Default")
      (node (ref "U3") (pin "15") (pinfunction "DOUT_15") (pintype "output"))
      (node (ref "U6") (pin "H5") (pinfunction "1_H5") (pintype "bidirectional"))
    )
    (net (code "20") (name "AD_SCLK") (class "Default")
      (node (ref "U3") (pin "16") (pinfunction "SCLK_16") (pintype "input"))
      (node (ref "U6") (pin "G6") (pinfunction "1_G6") (pintype "bidirectional"))
    )
    (net (code "21") (name "AIN0") (class "Default")
      (node (ref "J6") (pin "P$2") (pinfunction "P2_P$2") (pintype "bidirectional"))
      (node (ref "U3") (pin "4") (pinfunction "AIN0_4") (pintype "input"))
    )
    (net (code "22") (name "AIN1") (class "Default")
      (node (ref "J4") (pin "P$2") (pinfunction "P2_P$2") (pintype "bidirectional"))
      (node (ref "U3") (pin "5") (pinfunction "AIN1_5") (pintype "input"))
    )
    (net (code "23") (name "AIN2") (class "Default")
      (node (ref "J6") (pin "P$3") (pinfunction "P3_P$3") (pintype "bidirectional"))
      (node (ref "U3") (pin "6") (pinfunction "AIN2_6") (pintype "input"))
    )
    (net (code "24") (name "AIN3") (class "Default")
      (node (ref "J4") (pin "P$3") (pinfunction "P3_P$3") (pintype "bidirectional"))
      (node (ref "U3") (pin "7") (pinfunction "AIN3_7") (pintype "input"))
    )
    (net (code "25") (name "AIN4") (class "Default")
      (node (ref "J6") (pin "P$4") (pinfunction "P4_P$4") (pintype "bidirectional"))
      (node (ref "U3") (pin "8") (pinfunction "AIN4_8") (pintype "input"))
    )
    (net (code "26") (name "AIN5") (class "Default")
      (node (ref "J4") (pin "P$4") (pinfunction "P4_P$4") (pintype "bidirectional"))
      (node (ref "U3") (pin "9") (pinfunction "AIN5_9") (pintype "input"))
    )
    (net (code "27") (name "AIN6") (class "Default")
      (node (ref "J6") (pin "P$5") (pinfunction "P5_P$5") (pintype "bidirectional"))
      (node (ref "U3") (pin "10") (pinfunction "AIN6_10") (pintype "input"))
    )
    (net (code "28") (name "AIN7") (class "Default")
      (node (ref "J4") (pin "P$5") (pinfunction "P5_P$5") (pintype "bidirectional"))
      (node (ref "U3") (pin "11") (pinfunction "AIN7_11") (pintype "input"))
    )
    (net (code "29") (name "AUDIO1") (class "Default")
      (node (ref "R19") (pin "1") (pinfunction "1_1") (pintype "passive"))
      (node (ref "U6") (pin "B8") (pinfunction "1_B8") (pintype "bidirectional"))
    )
    (net (code "30") (name "AUDIO2") (class "Default")
      (node (ref "R20") (pin "1") (pinfunction "1_1") (pintype "passive"))
      (node (ref "U6") (pin "A8") (pinfunction "1_A8") (pintype "bidirectional"))
    )
    (net (code "31") (name "A_TMDS0_N") (class "Default")
      (node (ref "J3") (pin "9") (pinfunction "DATA0-_9") (pintype "bidirectional"))
      (node (ref "U6") (pin "A13") (pinfunction "1_A13") (pintype "bidirectional"))
    )
    (net (code "32") (name "A_TMDS0_P") (class "Default")
      (node (ref "J3") (pin "7") (pinfunction "DATA0+_7") (pintype "bidirectional"))
      (node (ref "U6") (pin "C13") (pinfunction "1_C13") (pintype "bidirectional"))
    )
    (net (code "33") (name "A_TMDS1_N") (class "Default")
      (node (ref "J3") (pin "6") (pinfunction "DATA1-_6") (pintype "bidirectional"))
      (node (ref "U6") (pin "A12") (pinfunction "1_A12") (pintype "bidirectional"))
    )
    (net (code "34") (name "A_TMDS1_P") (class "Default")
      (node (ref "J3") (pin "4") (pinfunction "DATA1+_4") (pintype "bidirectional"))
      (node (ref "U6") (pin "B12") (pinfunction "1_B12") (pintype "bidirectional"))
    )
    (net (code "35") (name "A_TMDS2_N") (class "Default")
      (node (ref "J3") (pin "3") (pinfunction "DATA2-_3") (pintype "bidirectional"))
      (node (ref "U6") (pin "A11") (pinfunction "1_A11") (pintype "bidirectional"))
    )
    (net (code "36") (name "A_TMDS2_P") (class "Default")
      (node (ref "J3") (pin "1") (pinfunction "DATA2+_1") (pintype "bidirectional"))
      (node (ref "U6") (pin "C11") (pinfunction "1_C11") (pintype "bidirectional"))
    )
    (net (code "37") (name "A_TMDS_CLK_N") (class "Default")
      (node (ref "J3") (pin "12") (pinfunction "CLOCK-_12") (pintype "bidirectional"))
      (node (ref "U6") (pin "A14") (pinfunction "1_A14") (pintype "bidirectional"))
    )
    (net (code "38") (name "A_TMDS_CLK_P") (class "Default")
      (node (ref "J3") (pin "10") (pinfunction "CLOCK+_10") (pintype "bidirectional"))
      (node (ref "U6") (pin "B14") (pinfunction "1_B14") (pintype "bidirectional"))
    )
    (net (code "39") (name "BS0") (class "Default")
      (node (ref "U6") (pin "R14") (pinfunction "1_R14") (pintype "bidirectional"))
      (node (ref "U9") (pin "20") (pinfunction "P$1_20") (pintype "bidirectional"))
    )
    (net (code "40") (name "BS1") (class "Default")
      (node (ref "U6") (pin "T14") (pinfunction "1_T14") (pintype "bidirectional"))
      (node (ref "U9") (pin "21") (pinfunction "P$1_21") (pintype "bidirectional"))
    )
    (net (code "41") (name "CAS#") (class "Default")
      (node (ref "U6") (pin "T4") (pinfunction "1_T4") (pintype "bidirectional"))
      (node (ref "U9") (pin "17") (pinfunction "P$1_17") (pintype "bidirectional"))
    )
    (net (code "42") (name "CKE") (class "Default")
      (node (ref "U6") (pin "H16") (pinfunction "1_H16") (pintype "bidirectional"))
      (node (ref "U9") (pin "37") (pinfunction "P$1_37") (pintype "bidirectional"))
    )
    (net (code "43") (name "D0") (class "Default")
      (node (ref "U6") (pin "T13") (pinfunction "1_T13") (pintype "bidirectional"))
      (node (ref "U9") (pin "2") (pinfunction "P$1_2") (pintype "bidirectional"))
    )
    (net (code "44") (name "D1") (class "Default")
      (node (ref "U6") (pin "T12") (pinfunction "1_T12") (pintype "bidirectional"))
      (node (ref "U9") (pin "4") (pinfunction "P$1_4") (pintype "bidirectional"))
    )
    (net (code "45") (name "D2") (class "Default")
      (node (ref "U6") (pin "R12") (pinfunction "1_R12") (pintype "bidirectional"))
      (node (ref "U9") (pin "5") (pinfunction "P$1_5") (pintype "bidirectional"))
    )
    (net (code "46") (name "D3") (class "Default")
      (node (ref "U6") (pin "T9") (pinfunction "1_T9") (pintype "bidirectional"))
      (node (ref "U9") (pin "7") (pinfunction "P$1_7") (pintype "bidirectional"))
    )
    (net (code "47") (name "D4") (class "Default")
      (node (ref "U6") (pin "R9") (pinfunction "1_R9") (pintype "bidirectional"))
      (node (ref "U9") (pin "8") (pinfunction "P$1_8") (pintype "bidirectional"))
    )
    (net (code "48") (name "D5") (class "Default")
      (node (ref "U6") (pin "T7") (pinfunction "1_T7") (pintype "bidirectional"))
      (node (ref "U9") (pin "10") (pinfunction "P$1_10") (pintype "bidirectional"))
    )
    (net (code "49") (name "D6") (class "Default")
      (node (ref "U6") (pin "R7") (pinfunction "1_R7") (pintype "bidirectional"))
      (node (ref "U9") (pin "11") (pinfunction "P$1_11") (pintype "bidirectional"))
    )
    (net (code "50") (name "D7") (class "Default")
      (node (ref "U6") (pin "T6") (pinfunction "1_T6") (pintype "bidirectional"))
      (node (ref "U9") (pin "13") (pinfunction "P$1_13") (pintype "bidirectional"))
    )
    (net (code "51") (name "D8") (class "Default")
      (node (ref "U6") (pin "F16") (pinfunction "1_F16") (pintype "bidirectional"))
      (node (ref "U9") (pin "42") (pinfunction "P$1_42") (pintype "bidirectional"))
    )
    (net (code "52") (name "D9") (class "Default")
      (node (ref "U6") (pin "E15") (pinfunction "1_E15") (pintype "bidirectional"))
      (node (ref "U9") (pin "44") (pinfunction "P$1_44") (pintype "bidirectional"))
    )
    (net (code "53") (name "D10") (class "Default")
      (node (ref "U6") (pin "E16") (pinfunction "1_E16") (pintype "bidirectional"))
      (node (ref "U9") (pin "45") (pinfunction "P$1_45") (pintype "bidirectional"))
    )
    (net (code "54") (name "D11") (class "Default")
      (node (ref "U6") (pin "D16") (pinfunction "1_D16") (pintype "bidirectional"))
      (node (ref "U9") (pin "47") (pinfunction "P$1_47") (pintype "bidirectional"))
    )
    (net (code "55") (name "D12") (class "Default")
      (node (ref "U6") (pin "B16") (pinfunction "1_B16") (pintype "bidirectional"))
      (node (ref "U9") (pin "48") (pinfunction "P$1_48") (pintype "bidirectional"))
    )
    (net (code "56") (name "D13") (class "Default")
      (node (ref "U6") (pin "B15") (pinfunction "1_B15") (pintype "bidirectional"))
      (node (ref "U9") (pin "50") (pinfunction "P$1_50") (pintype "bidirectional"))
    )
    (net (code "57") (name "D14") (class "Default")
      (node (ref "U6") (pin "C16") (pinfunction "1_C16") (pintype "bidirectional"))
      (node (ref "U9") (pin "51") (pinfunction "P$1_51") (pintype "bidirectional"))
    )
    (net (code "58") (name "D15") (class "Default")
      (node (ref "U6") (pin "C15") (pinfunction "1_C15") (pintype "bidirectional"))
      (node (ref "U9") (pin "53") (pinfunction "P$1_53") (pintype "bidirectional"))
    )
    (net (code "59") (name "EECLK") (class "Default")
      (node (ref "R13") (pin "1") (pinfunction "1_1") (pintype "passive"))
      (node (ref "U1") (pin "4") (pinfunction "CLK_4") (pintype "input"))
      (node (ref "U2") (pin "62") (pinfunction "EECLK_62") (pintype "bidirectional"))
    )
    (net (code "60") (name "EECS") (class "Default")
      (node (ref "R10") (pin "1") (pinfunction "1_1") (pintype "passive"))
      (node (ref "U1") (pin "5") (pinfunction "CS_5") (pintype "input"))
      (node (ref "U2") (pin "63") (pinfunction "EECS_63") (pintype "bidirectional"))
    )
    (net (code "61") (name "EEDATA") (class "Default")
      (node (ref "R11") (pin "2") (pinfunction "2_2") (pintype "passive"))
      (node (ref "U1") (pin "3") (pinfunction "DI_3") (pintype "input"))
      (node (ref "U2") (pin "61") (pinfunction "EEDATA_61") (pintype "bidirectional"))
    )
    (net (code "62") (name "FLASH-CS#") (class "Default")
      (node (ref "U10") (pin "1") (pinfunction "1_1") (pintype "input"))
      (node (ref "U6") (pin "T3") (pinfunction "1_T3") (pintype "bidirectional"))
    )
    (net (code "63") (name "FPGA-CCLK") (class "Default")
      (node (ref "U10") (pin "6") (pinfunction "1_6") (pintype "input"))
      (node (ref "U6") (pin "R11") (pinfunction "1_R11") (pintype "bidirectional"))
    )
    (net (code "64") (name "FPGA-CLK-1") (class "Default")
      (node (ref "U6") (pin "K3") (pinfunction "1_K3") (pintype "bidirectional"))
      (node (ref "U8") (pin "3") (pinfunction "OUT_3") (pintype "bidirectional"))
    )
    (net (code "65") (name "FPGA-CLK-2") (class "Default")
      (node (ref "U6") (pin "J4") (pinfunction "1_J4") (pintype "bidirectional"))
      (node (ref "U7") (pin "3") (pinfunction "OUT_3") (pintype "bidirectional"))
    )
    (net (code "66") (name "FPGA-DONE") (class "Default")
      (node (ref "U6") (pin "P13") (pinfunction "1_P13") (pintype "output"))
    )
    (net (code "67") (name "FPGA-INIT#") (class "Default")
      (node (ref "U6") (pin "R3") (pinfunction "1_R3") (pintype "bidirectional"))
    )
    (net (code "68") (name "FPGA-MISO") (class "Default")
      (node (ref "U10") (pin "2") (pinfunction "1_2") (pintype "output"))
      (node (ref "U6") (pin "P10") (pinfunction "1_P10") (pintype "bidirectional"))
    )
    (net (code "69") (name "FPGA-MOSI") (class "Default")
      (node (ref "U10") (pin "5") (pinfunction "1_5") (pintype "input"))
      (node (ref "U6") (pin "T10") (pinfunction "1_T10") (pintype "bidirectional"))
    )
    (net (code "70") (name "FPGA_SCL") (class "Default")
      (node (ref "RN5") (pin "7") (pinfunction "2_7") (pintype "passive"))
      (node (ref "U11") (pin "3") (pinfunction "SCL1_3") (pintype "bidirectional"))
      (node (ref "U6") (pin "C1") (pinfunction "1_C1") (pintype "bidirectional"))
    )
    (net (code "71") (name "FPGA_SDA") (class "Default")
      (node (ref "RN5") (pin "8") (pinfunction "2_8") (pintype "passive"))
      (node (ref "U11") (pin "4") (pinfunction "SDA1_4") (pintype "bidirectional"))
      (node (ref "U6") (pin "B1") (pinfunction "1_B1") (pintype "bidirectional"))
    )
    (net (code "72") (name "FTDI_D0") (class "Default")
      (node (ref "U2") (pin "38") (pinfunction "BDBUS0/TXD/TCK/SK_38") (pintype "bidirectional"))
      (node (ref "U6") (pin "M7") (pinfunction "1_M7") (pintype "bidirectional"))
    )
    (net (code "73") (name "FTDI_D1") (class "Default")
      (node (ref "U2") (pin "39") (pinfunction "BDBUS1/RXD/TDI/DO_39") (pintype "bidirectional"))
      (node (ref "U6") (pin "N6") (pinfunction "1_N6") (pintype "bidirectional"))
    )
    (net (code "74") (name "FTDI_D2") (class "Default")
      (node (ref "U2") (pin "40") (pinfunction "BDBUS2/RTS#/TDO/DI_40") (pintype "bidirectional"))
      (node (ref "U6") (pin "M6") (pinfunction "1_M6") (pintype "bidirectional"))
    )
    (net (code "75") (name "FTDI_D3") (class "Default")
      (node (ref "U2") (pin "41") (pinfunction "BDBUS3/CTS#/TMS/CS_41") (pintype "bidirectional"))
      (node (ref "U6") (pin "P5") (pinfunction "1_P5") (pintype "bidirectional"))
    )
    (net (code "76") (name "FTDI_D4") (class "Default")
      (node (ref "U2") (pin "43") (pinfunction "BDBUS4/DTR#/GPIOL0_43") (pintype "bidirectional"))
      (node (ref "U6") (pin "N5") (pinfunction "1_N5") (pintype "bidirectional"))
    )
    (net (code "77") (name "FTDI_D5") (class "Default")
      (node (ref "U2") (pin "44") (pinfunction "BDBUS5/DSR#/GPIOL1_44") (pintype "bidirectional"))
      (node (ref "U6") (pin "P4") (pinfunction "1_P4") (pintype "bidirectional"))
    )
    (net (code "78") (name "FTDI_D6") (class "Default")
      (node (ref "U2") (pin "45") (pinfunction "BDBUS6/DCD#/GPIOL2_45") (pintype "bidirectional"))
      (node (ref "U6") (pin "P2") (pinfunction "1_P2") (pintype "bidirectional"))
    )
    (net (code "79") (name "FTDI_D7") (class "Default")
      (node (ref "U2") (pin "46") (pinfunction "BDBUS7/RI#/GPIOL3_46") (pintype "bidirectional"))
      (node (ref "U6") (pin "P1") (pinfunction "1_P1") (pintype "bidirectional"))
    )
    (net (code "80") (name "FTDI_RD") (class "Default")
      (node (ref "U2") (pin "53") (pinfunction "BCBUS2_53") (pintype "bidirectional"))
      (node (ref "U6") (pin "M1") (pinfunction "1_M1") (pintype "bidirectional"))
    )
    (net (code "81") (name "FTDI_RXF") (class "Default")
      (node (ref "U2") (pin "48") (pinfunction "BCBUS0/GPIOH1_48") (pintype "bidirectional"))
      (node (ref "U6") (pin "N3") (pinfunction "1_N3") (pintype "bidirectional"))
    )
    (net (code "82") (name "FTDI_SIWUA") (class "Default")
      (node (ref "U2") (pin "55") (pinfunction "BCBUS4/TXLED#/GPIOH4_55") (pintype "bidirectional"))
      (node (ref "U6") (pin "M3") (pinfunction "1_M3") (pintype "bidirectional"))
    )
    (net (code "83") (name "FTDI_TXE") (class "Default")
      (node (ref "U2") (pin "52") (pinfunction "BCBUS1/GPIOH2_52") (pintype "bidirectional"))
      (node (ref "U6") (pin "N1") (pinfunction "1_N1") (pintype "bidirectional"))
    )
    (net (code "84") (name "FTDI_WR") (class "Default")
      (node (ref "U2") (pin "54") (pinfunction "BCBUS3/RXLED#/GPIOH3_54") (pintype "bidirectional"))
      (node (ref "U6") (pin "M2") (pinfunction "1_M2") (pintype "bidirectional"))
    )
    (net (code "85") (name "GND") (class "Default")
      (node (ref "C1") (pin "2") (pinfunction "2_2") (pintype "passive"))
      (node (ref "C10") (pin "2") (pinfunction "2_2") (pintype "passive"))
      (node (ref "C11") (pin "2") (pinfunction "2_2") (pintype "passive"))
      (node (ref "C12") (pin "2") (pinfunction "2_2") (pintype "passive"))
      (node (ref "C13") (pin "2") (pinfunction "2_2") (pintype "passive"))
      (node (ref "C14") (pin "2") (pinfunction "2_2") (pintype "passive"))
      (node (ref "C15") (pin "2") (pinfunction "2_2") (pintype "passive"))
      (node (ref "C16") (pin "2") (pinfunction "2_2") (pintype "passive"))
      (node (ref "C17") (pin "2") (pinfunction "2_2") (pintype "passive"))
      (node (ref "C18") (pin "2") (pinfunction "2_2") (pintype "passive"))
      (node (ref "C19") (pin "2") (pinfunction "2_2") (pintype "passive"))
      (node (ref "C2") (pin "2") (pinfunction "2_2") (pintype "passive"))
      (node (ref "C20") (pin "2") (pinfunction "2_2") (pintype "passive"))
      (node (ref "C21") (pin "2") (pinfunction "2_2") (pintype "passive"))
      (node (ref "C22") (pin "2") (pinfunction "2_2") (pintype "passive"))
      (node (ref "C23") (pin "2") (pinfunction "2_2") (pintype "passive"))
      (node (ref "C24") (pin "2") (pinfunction "2_2") (pintype "passive"))
      (node (ref "C25") (pin "2") (pinfunction "2_2") (pintype "passive"))
      (node (ref "C26") (pin "2") (pinfunction "2_2") (pintype "passive"))
      (node (ref "C27") (pin "2") (pinfunction "2_2") (pintype "passive"))
      (node (ref "C28") (pin "2") (pinfunction "2_2") (pintype "passive"))
      (node (ref "C29") (pin "2") (pinfunction "2_2") (pintype "passive"))
      (node (ref "C3") (pin "2") (pinfunction "2_2") (pintype "passive"))
      (node (ref "C30") (pin "2") (pinfunction "2_2") (pintype "passive"))
      (node (ref "C31") (pin "2") (pinfunction "2_2") (pintype "passive"))
      (node (ref "C32") (pin "2") (pinfunction "2_2") (pintype "passive"))
      (node (ref "C33") (pin "2") (pinfunction "2_2") (pintype "passive"))
      (node (ref "C34") (pin "2") (pinfunction "2_2") (pintype "passive"))
      (node (ref "C35") (pin "2") (pinfunction "2_2") (pintype "passive"))
      (node (ref "C36") (pin "2") (pinfunction "2_2") (pintype "passive"))
      (node (ref "C37") (pin "2") (pinfunction "2_2") (pintype "passive"))
      (node (ref "C38") (pin "2") (pinfunction "2_2") (pintype "passive"))
      (node (ref "C39") (pin "2") (pinfunction "2_2") (pintype "passive"))
      (node (ref "C4") (pin "2") (pinfunction "2_2") (pintype "passive"))
      (node (ref "C40") (pin "2") (pinfunction "2_2") (pintype "passive"))
      (node (ref "C5") (pin "2") (pinfunction "2_2") (pintype "passive"))
      (node (ref "C6") (pin "2") (pinfunction "2_2") (pintype "passive"))
      (node (ref "C7") (pin "2") (pinfunction "2_2") (pintype "passive"))
      (node (ref "C8") (pin "2") (pinfunction "2_2") (pintype "passive"))
      (node (ref "C9") (pin "2") (pinfunction "2_2") (pintype "passive"))
      (node (ref "J2") (pin "11") (pinfunction "CLOCKSHIELD_11") (pintype "bidirectional"))
      (node (ref "J2") (pin "14") (pinfunction "RES_14") (pintype "bidirectional"))
      (node (ref "J2") (pin "17") (pinfunction "DDC/CEC-GRND_17") (pintype "bidirectional"))
      (node (ref "J2") (pin "2") (pinfunction "DATA2SHIELD_2") (pintype "bidirectional"))
      (node (ref "J2") (pin "5") (pinfunction "DATA1SHIELD_5") (pintype "bidirectional"))
      (node (ref "J2") (pin "8") (pinfunction "DATA0SHIELD_8") (pintype "bidirectional"))
      (node (ref "J3") (pin "11") (pinfunction "CLOCKSHIELD_11") (pintype "bidirectional"))
      (node (ref "J3") (pin "14") (pinfunction "RES_14") (pintype "bidirectional"))
      (node (ref "J3") (pin "17") (pinfunction "DDC/CEC-GRND_17") (pintype "bidirectional"))
      (node (ref "J3") (pin "2") (pinfunction "DATA2SHIELD_2") (pintype "bidirectional"))
      (node (ref "J3") (pin "5") (pinfunction "DATA1SHIELD_5") (pintype "bidirectional"))
      (node (ref "J3") (pin "8") (pinfunction "DATA0SHIELD_8") (pintype "bidirectional"))
      (node (ref "J4") (pin "P$1") (pinfunction "P1_P$1") (pintype "bidirectional"))
      (node (ref "J4") (pin "P$17") (pinfunction "P17_P$17") (pintype "bidirectional"))
      (node (ref "J4") (pin "P$6") (pinfunction "P6_P$6") (pintype "bidirectional"))
      (node (ref "J4") (pin "P$9") (pinfunction "P9_P$9") (pintype "bidirectional"))
      (node (ref "J5") (pin "G1") (pinfunction "GND0_G1") (pintype "bidirectional"))
      (node (ref "J5") (pin "G2") (pinfunction "GND1_G2") (pintype "bidirectional"))
      (node (ref "J5") (pin "G3") (pinfunction "GND2_G3") (pintype "bidirectional"))
      (node (ref "J5") (pin "G4") (pinfunction "GND3_G4") (pintype "bidirectional"))
      (node (ref "J5") (pin "T6") (pinfunction "VSS_T6") (pintype "bidirectional"))
      (node (ref "J6") (pin "P$1") (pinfunction "P1_P$1") (pintype "bidirectional"))
      (node (ref "J6") (pin "P$13") (pinfunction "P13_P$13") (pintype "bidirectional"))
      (node (ref "J6") (pin "P$21") (pinfunction "P21_P$21") (pintype "bidirectional"))
      (node (ref "J6") (pin "P$6") (pinfunction "P6_P$6") (pintype "bidirectional"))
      (node (ref "JP5") (pin "EARTH") (pinfunction "EARTH_EARTH") (pintype "bidirectional"))
      (node (ref "R1") (pin "1") (pinfunction "1_1") (pintype "passive"))
      (node (ref "R15") (pin "1") (pinfunction "1_1") (pintype "passive"))
      (node (ref "R17") (pin "1") (pinfunction "1_1") (pintype "passive"))
      (node (ref "R2") (pin "1") (pinfunction "1_1") (pintype "passive"))
      (node (ref "R21") (pin "1") (pinfunction "1_1") (pintype "passive"))
      (node (ref "R3") (pin "1") (pinfunction "1_1") (pintype "passive"))
      (node (ref "R4") (pin "1") (pinfunction "1_1") (pintype "passive"))
      (node (ref "R5") (pin "1") (pinfunction "1_1") (pintype "passive"))
      (node (ref "RN1") (pin "1") (pinfunction "1_1") (pintype "passive"))
      (node (ref "RN1") (pin "2") (pinfunction "1_2") (pintype "passive"))
      (node (ref "RN1") (pin "3") (pinfunction "1_3") (pintype "passive"))
      (node (ref "RN1") (pin "4") (pinfunction "1_4") (pintype "passive"))
      (node (ref "RN2") (pin "1") (pinfunction "1_1") (pintype "passive"))
      (node (ref "RN2") (pin "2") (pinfunction "1_2") (pintype "passive"))
      (node (ref "RN2") (pin "3") (pinfunction "1_3") (pintype "passive"))
      (node (ref "RN2") (pin "4") (pinfunction "1_4") (pintype "passive"))
      (node (ref "S1") (pin "1") (pinfunction "1_1") (pintype "passive"))
      (node (ref "S1") (pin "2") (pinfunction "2_2") (pintype "passive"))
      (node (ref "S2") (pin "1") (pinfunction "1_1") (pintype "passive"))
      (node (ref "S2") (pin "2") (pinfunction "2_2") (pintype "passive"))
      (node (ref "S2") (pin "3") (pinfunction "3_3") (pintype "passive"))
      (node (ref "S2") (pin "4") (pinfunction "4_4") (pintype "passive"))
      (node (ref "U$7") (pin "P$12") (pinfunction "P12_P$12") (pintype "bidirectional"))
      (node (ref "U$7") (pin "P$20") (pinfunction "P20_P$20") (pintype "bidirectional"))
      (node (ref "U$7") (pin "P$4") (pinfunction "P4_P$4") (pintype "bidirectional"))
      (node (ref "U$8") (pin "P$16") (pinfunction "P16_P$16") (pintype "bidirectional"))
      (node (ref "U$8") (pin "P$24") (pinfunction "P24_P$24") (pintype "bidirectional"))
      (node (ref "U$8") (pin "P$8") (pinfunction "P8_P$8") (pintype "bidirectional"))
      (node (ref "U1") (pin "2") (pinfunction "GND_2") (pintype "power_in"))
      (node (ref "U10") (pin "4") (pinfunction "1_4") (pintype "input"))
      (node (ref "U11") (pin "1") (pinfunction "GND_1") (pintype "bidirectional"))
      (node (ref "U2") (pin "1") (pinfunction "GND0_1") (pintype "bidirectional"))
      (node (ref "U2") (pin "10") (pinfunction "AGND_10") (pintype "bidirectional"))
      (node (ref "U2") (pin "11") (pinfunction "GND2_11") (pintype "bidirectional"))
      (node (ref "U2") (pin "13") (pinfunction "TEST_13") (pintype "bidirectional"))
      (node (ref "U2") (pin "15") (pinfunction "GND3_15") (pintype "bidirectional"))
      (node (ref "U2") (pin "25") (pinfunction "GND4_25") (pintype "bidirectional"))
      (node (ref "U2") (pin "35") (pinfunction "GND5_35") (pintype "bidirectional"))
      (node (ref "U2") (pin "47") (pinfunction "GND6_47") (pintype "bidirectional"))
      (node (ref "U2") (pin "5") (pinfunction "GND1_5") (pintype "bidirectional"))
      (node (ref "U2") (pin "51") (pinfunction "GND7_51") (pintype "bidirectional"))
      (node (ref "U3") (pin "12") (pinfunction "DGND_12") (pintype "power_in"))
      (node (ref "U3") (pin "3") (pinfunction "AGND_3") (pintype "power_in"))
      (node (ref "U4") (pin "1") (pinfunction "GND_1") (pintype "input"))
      (node (ref "U5") (pin "1") (pinfunction "GND_1") (pintype "input"))
      (node (ref "U6") (pin "A1") (pinfunction "1_A1") (pintype "input"))
      (node (ref "U6") (pin "A16") (pinfunction "1_A16") (pintype "input"))
      (node (ref "U6") (pin "B11") (pinfunction "1_B11") (pintype "input"))
      (node (ref "U6") (pin "B7") (pinfunction "1_B7") (pintype "input"))
      (node (ref "U6") (pin "C4") (pinfunction "1_C4") (pintype "bidirectional"))
      (node (ref "U6") (pin "D13") (pinfunction "1_D13") (pintype "input"))
      (node (ref "U6") (pin "D4") (pinfunction "1_D4") (pintype "input"))
      (node (ref "U6") (pin "E9") (pinfunction "1_E9") (pintype "input"))
      (node (ref "U6") (pin "G15") (pinfunction "1_G15") (pintype "input"))
      (node (ref "U6") (pin "G2") (pinfunction "1_G2") (pintype "input"))
      (node (ref "U6") (pin "G8") (pinfunction "1_G8") (pintype "input"))
      (node (ref "U6") (pin "H12") (pinfunction "1_H12") (pintype "input"))
      (node (ref "U6") (pin "H7") (pinfunction "1_H7") (pintype "input"))
      (node (ref "U6") (pin "H9") (pinfunction "1_H9") (pintype "input"))
      (node (ref "U6") (pin "J5") (pinfunction "1_J5") (pintype "input"))
      (node (ref "U6") (pin "J8") (pinfunction "1_J8") (pintype "input"))
      (node (ref "U6") (pin "K7") (pinfunction "1_K7") (pintype "input"))
      (node (ref "U6") (pin "K9") (pinfunction "1_K9") (pintype "input"))
      (node (ref "U6") (pin "L15") (pinfunction "1_L15") (pintype "input"))
      (node (ref "U6") (pin "L2") (pinfunction "1_L2") (pintype "input"))
      (node (ref "U6") (pin "M8") (pinfunction "1_M8") (pintype "input"))
      (node (ref "U6") (pin "N11") (pinfunction "1_N11") (pintype "bidirectional"))
      (node (ref "U6") (pin "N13") (pinfunction "1_N13") (pintype "input"))
      (node (ref "U6") (pin "P14") (pinfunction "1_P14") (pintype "input"))
      (node (ref "U6") (pin "P3") (pinfunction "1_P3") (pintype "input"))
      (node (ref "U6") (pin "R10") (pinfunction "1_R10") (pintype "input"))
      (node (ref "U6") (pin "R6") (pinfunction "1_R6") (pintype "input"))
      (node (ref "U6") (pin "T1") (pinfunction "1_T1") (pintype "input"))
      (node (ref "U6") (pin "T16") (pinfunction "1_T16") (pintype "input"))
      (node (ref "U7") (pin "2") (pinfunction "GND_2") (pintype "bidirectional"))
      (node (ref "U8") (pin "2") (pinfunction "GND_2") (pintype "bidirectional"))
      (node (ref "U9") (pin "12") (pinfunction "P$1_12") (pintype "bidirectional"))
      (node (ref "U9") (pin "28") (pinfunction "P$1_28") (pintype "bidirectional"))
      (node (ref "U9") (pin "41") (pinfunction "P$1_41") (pintype "bidirectional"))
      (node (ref "U9") (pin "46") (pinfunction "P$1_46") (pintype "bidirectional"))
      (node (ref "U9") (pin "52") (pinfunction "P$1_52") (pintype "bidirectional"))
      (node (ref "U9") (pin "54") (pinfunction "P$1_54") (pintype "bidirectional"))
      (node (ref "U9") (pin "6") (pinfunction "P$1_6") (pintype "bidirectional"))
      (node (ref "X1") (pin "5") (pinfunction "5_5") (pintype "input"))
    )
    (net (code "86") (name "LDQM") (class "Default")
      (node (ref "U6") (pin "T5") (pinfunction "1_T5") (pintype "bidirectional"))
      (node (ref "U9") (pin "15") (pinfunction "P$1_15") (pintype "bidirectional"))
    )
    (net (code "87") (name "LED1") (class "Default")
      (node (ref "LED1") (pin "A") (pinfunction "A_A") (pintype "passive"))
      (node (ref "U6") (pin "P11") (pinfunction "1_P11") (pintype "bidirectional"))
    )
    (net (code "88") (name "LED2") (class "Default")
      (node (ref "LED2") (pin "A") (pinfunction "A_A") (pintype "passive"))
      (node (ref "U6") (pin "N9") (pinfunction "1_N9") (pintype "bidirectional"))
    )
    (net (code "89") (name "LED3") (class "Default")
      (node (ref "LED3") (pin "A") (pinfunction "A_A") (pintype "passive"))
      (node (ref "U6") (pin "P9") (pinfunction "1_P9") (pintype "bidirectional"))
    )
    (net (code "90") (name "LED4") (class "Default")
      (node (ref "LED4") (pin "A") (pinfunction "A_A") (pintype "passive"))
      (node (ref "U6") (pin "M9") (pinfunction "1_M9") (pintype "bidirectional"))
    )
    (net (code "91") (name "LED5") (class "Default")
      (node (ref "LED5") (pin "A") (pinfunction "A_A") (pintype "passive"))
      (node (ref "U6") (pin "N8") (pinfunction "1_N8") (pintype "bidirectional"))
    )
    (net (code "92") (name "LED6") (class "Default")
      (node (ref "LED6") (pin "A") (pinfunction "A_A") (pintype "passive"))
      (node (ref "U6") (pin "P7") (pinfunction "1_P7") (pintype "bidirectional"))
    )
    (net (code "93") (name "LED7") (class "Default")
      (node (ref "LED7") (pin "A") (pinfunction "A_A") (pintype "passive"))
      (node (ref "U6") (pin "P8") (pinfunction "1_P8") (pintype "bidirectional"))
    )
    (net (code "94") (name "LED8") (class "Default")
      (node (ref "LED8") (pin "A") (pinfunction "A_A") (pintype "passive"))
      (node (ref "U6") (pin "T8") (pinfunction "1_T8") (pintype "bidirectional"))
    )
    (net (code "95") (name "Net-(C14-Pad1)") (class "Default")
      (node (ref "C14") (pin "1") (pinfunction "1_1") (pintype "passive"))
      (node (ref "JP5") (pin "TIP") (pinfunction "TIP_TIP") (pintype "bidirectional"))
      (node (ref "R20") (pin "2") (pinfunction "2_2") (pintype "passive"))
    )
    (net (code "96") (name "Net-(C15-Pad1)") (class "Default")
      (node (ref "C15") (pin "1") (pinfunction "1_1") (pintype "passive"))
      (node (ref "JP5") (pin "RING1") (pinfunction "RING1_RING1") (pintype "bidirectional"))
      (node (ref "R19") (pin "2") (pinfunction "2_2") (pintype "passive"))
    )
    (net (code "97") (name "Net-(C37-Pad1)") (class "Default")
      (node (ref "C37") (pin "1") (pinfunction "1_1") (pintype "passive"))
      (node (ref "R1") (pin "2") (pinfunction "2_2") (pintype "passive"))
      (node (ref "X1") (pin "M1") (pinfunction "M1_M1") (pintype "bidirectional"))
      (node (ref "X1") (pin "M2") (pinfunction "M2_M2") (pintype "bidirectional"))
      (node (ref "X1") (pin "M3") (pinfunction "M3_M3") (pintype "bidirectional"))
      (node (ref "X1") (pin "M4") (pinfunction "M4_M4") (pintype "bidirectional"))
    )
    (net (code "98") (name "Net-(C39-Pad1)") (class "Default")
      (node (ref "C39") (pin "1") (pinfunction "1_1") (pintype "passive"))
      (node (ref "J2") (pin "SH1") (pinfunction "SH1_SH1") (pintype "bidirectional"))
      (node (ref "J2") (pin "SH2") (pinfunction "SH2_SH2") (pintype "bidirectional"))
      (node (ref "J2") (pin "SH3") (pinfunction "SH3_SH3") (pintype "bidirectional"))
      (node (ref "J2") (pin "SH4") (pinfunction "SH4_SH4") (pintype "bidirectional"))
      (node (ref "R2") (pin "2") (pinfunction "2_2") (pintype "passive"))
    )
    (net (code "99") (name "Net-(C40-Pad1)") (class "Default")
      (node (ref "C40") (pin "1") (pinfunction "1_1") (pintype "passive"))
      (node (ref "J3") (pin "SH1") (pinfunction "SH1_SH1") (pintype "bidirectional"))
      (node (ref "J3") (pin "SH2") (pinfunction "SH2_SH2") (pintype "bidirectional"))
      (node (ref "J3") (pin "SH3") (pinfunction "SH3_SH3") (pintype "bidirectional"))
      (node (ref "J3") (pin "SH4") (pinfunction "SH4_SH4") (pintype "bidirectional"))
      (node (ref "R3") (pin "2") (pinfunction "2_2") (pintype "passive"))
    )
    (net (code "100") (name "Net-(J2-DETECT)") (class "Default")
      (node (ref "J2") (pin "19") (pinfunction "DETECT_19") (pintype "bidirectional"))
      (node (ref "R14") (pin "2") (pinfunction "2_2") (pintype "passive"))
    )
    (net (code "101") (name "Net-(J2-SCL)") (class "Default")
      (node (ref "J2") (pin "15") (pinfunction "SCL_15") (pintype "bidirectional"))
      (node (ref "RN5") (pin "6") (pinfunction "2_6") (pintype "passive"))
      (node (ref "U11") (pin "6") (pinfunction "SCL2_6") (pintype "bidirectional"))
    )
    (net (code "102") (name "Net-(J2-SDA)") (class "Default")
      (node (ref "J2") (pin "16") (pinfunction "SDA_16") (pintype "bidirectional"))
      (node (ref "RN5") (pin "5") (pinfunction "2_5") (pintype "passive"))
      (node (ref "U11") (pin "5") (pinfunction "SDA2_5") (pintype "bidirectional"))
    )
    (net (code "103") (name "Net-(J3-DETECT)") (class "Default")
      (node (ref "J3") (pin "19") (pinfunction "DETECT_19") (pintype "bidirectional"))
      (node (ref "R17") (pin "2") (pinfunction "2_2") (pintype "passive"))
    )
    (net (code "104") (name "Net-(LED9-PadC)") (class "Default")
      (node (ref "LED9") (pin "C") (pinfunction "C_C") (pintype "passive"))
      (node (ref "R21") (pin "2") (pinfunction "2_2") (pintype "passive"))
    )
    (net (code "105") (name "Net-(Q1-2)") (class "Default")
      (node (ref "C10") (pin "1") (pinfunction "1_1") (pintype "passive"))
      (node (ref "Q1") (pin "3") (pinfunction "2_3") (pintype "passive"))
      (node (ref "U2") (pin "3") (pinfunction "OSC0_3") (pintype "bidirectional"))
    )
    (net (code "106") (name "Net-(RN1A-2)") (class "Default")
      (node (ref "LED4") (pin "C") (pinfunction "C_C") (pintype "passive"))
      (node (ref "RN1") (pin "8") (pinfunction "2_8") (pintype "passive"))
    )
    (net (code "107") (name "Net-(RN1B-2)") (class "Default")
      (node (ref "LED3") (pin "C") (pinfunction "C_C") (pintype "passive"))
      (node (ref "RN1") (pin "7") (pinfunction "2_7") (pintype "passive"))
    )
    (net (code "108") (name "Net-(RN1C-2)") (class "Default")
      (node (ref "LED2") (pin "C") (pinfunction "C_C") (pintype "passive"))
      (node (ref "RN1") (pin "6") (pinfunction "2_6") (pintype "passive"))
    )
    (net (code "109") (name "Net-(RN1D-2)") (class "Default")
      (node (ref "LED1") (pin "C") (pinfunction "C_C") (pintype "passive"))
      (node (ref "RN1") (pin "5") (pinfunction "2_5") (pintype "passive"))
    )
    (net (code "110") (name "Net-(RN2A-2)") (class "Default")
      (node (ref "LED6") (pin "C") (pinfunction "C_C") (pintype "passive"))
      (node (ref "RN2") (pin "8") (pinfunction "2_8") (pintype "passive"))
    )
    (net (code "111") (name "Net-(RN2B-2)") (class "Default")
      (node (ref "LED7") (pin "C") (pinfunction "C_C") (pintype "passive"))
      (node (ref "RN2") (pin "7") (pinfunction "2_7") (pintype "passive"))
    )
    (net (code "112") (name "Net-(RN2C-2)") (class "Default")
      (node (ref "LED5") (pin "C") (pinfunction "C_C") (pintype "passive"))
      (node (ref "RN2") (pin "6") (pinfunction "2_6") (pintype "passive"))
    )
    (net (code "113") (name "Net-(RN2D-2)") (class "Default")
      (node (ref "LED8") (pin "C") (pinfunction "C_C") (pintype "passive"))
      (node (ref "RN2") (pin "5") (pinfunction "2_5") (pintype "passive"))
    )
    (net (code "114") (name "Net-(RN3B-2)") (class "Default")
      (node (ref "R7") (pin "2") (pinfunction "2_2") (pintype "passive"))
      (node (ref "RN3") (pin "1") (pinfunction "1_1") (pintype "passive"))
      (node (ref "RN3") (pin "3") (pinfunction "2_3") (pintype "passive"))
      (node (ref "RN4") (pin "1") (pinfunction "1_1") (pintype "passive"))
      (node (ref "RN4") (pin "3") (pinfunction "2_3") (pintype "passive"))
      (node (ref "RN8") (pin "1") (pinfunction "1_1") (pintype "passive"))
      (node (ref "RN8") (pin "3") (pinfunction "2_3") (pintype "passive"))
      (node (ref "RN9") (pin "1") (pinfunction "1_1") (pintype "passive"))
      (node (ref "RN9") (pin "3") (pinfunction "2_3") (pintype "passive"))
    )
    (net (code "115") (name "Net-(U1-DO)") (class "Default")
      (node (ref "R11") (pin "1") (pinfunction "1_1") (pintype "passive"))
      (node (ref "R8") (pin "1") (pinfunction "1_1") (pintype "passive"))
      (node (ref "U1") (pin "1") (pinfunction "DO_1") (pintype "output"))
    )
    (net (code "116") (name "Net-(U2-DM)") (class "Default")
      (node (ref "U2") (pin "7") (pinfunction "DM_7") (pintype "bidirectional"))
      (node (ref "X1") (pin "2") (pinfunction "2_2") (pintype "input"))
    )
    (net (code "117") (name "Net-(U2-DP)") (class "Default")
      (node (ref "U2") (pin "8") (pinfunction "DP_8") (pintype "bidirectional"))
      (node (ref "X1") (pin "3") (pinfunction "3_3") (pintype "input"))
    )
    (net (code "118") (name "Net-(U2-OSCI)") (class "Default")
      (node (ref "C5") (pin "1") (pinfunction "1_1") (pintype "passive"))
      (node (ref "Q1") (pin "1") (pinfunction "1_1") (pintype "passive"))
      (node (ref "U2") (pin "2") (pinfunction "OSCI_2") (pintype "bidirectional"))
    )
    (net (code "119") (name "Net-(U2-REF)") (class "Default")
      (node (ref "R15") (pin "2") (pinfunction "2_2") (pintype "passive"))
      (node (ref "U2") (pin "6") (pinfunction "REF_6") (pintype "bidirectional"))
    )
    (net (code "120") (name "Net-(U2-RESET#)") (class "Default")
      (node (ref "R16") (pin "2") (pinfunction "2_2") (pintype "passive"))
      (node (ref "U2") (pin "14") (pinfunction "RESET#_14") (pintype "bidirectional"))
    )
    (net (code "121") (name "Net-(U2-VPHY)") (class "Default")
      (node (ref "C1") (pin "1") (pinfunction "1_1") (pintype "passive"))
      (node (ref "C3") (pin "1") (pinfunction "1_1") (pintype "passive"))
      (node (ref "L1") (pin "1") (pinfunction "1_1") (pintype "passive"))
      (node (ref "U2") (pin "4") (pinfunction "VPHY_4") (pintype "bidirectional"))
    )
    (net (code "122") (name "Net-(U2-VPLL)") (class "Default")
      (node (ref "C6") (pin "1") (pinfunction "1_1") (pintype "passive"))
      (node (ref "C8") (pin "1") (pinfunction "1_1") (pintype "passive"))
      (node (ref "L2") (pin "1") (pinfunction "1_1") (pintype "passive"))
      (node (ref "U2") (pin "9") (pinfunction "VPLL_9") (pintype "bidirectional"))
    )
    (net (code "123") (name "Net-(U3-VA)") (class "Default")
      (node (ref "C11") (pin "1") (pinfunction "1_1") (pintype "passive"))
      (node (ref "L3") (pin "1") (pinfunction "1_1") (pintype "passive"))
      (node (ref "U3") (pin "2") (pinfunction "VA_2") (pintype "power_in"))
    )
    (net (code "124") (name "Net-(U5-HS)") (class "Default")
      (node (ref "C31") (pin "1") (pinfunction "1_1") (pintype "passive"))
      (node (ref "U5") (pin "2") (pinfunction "OUT_2") (pintype "passive"))
      (node (ref "U5") (pin "4") (pinfunction "HS_4") (pintype "passive"))
    )
    (net (code "125") (name "Net-(U11-EN)") (class "Default")
      (node (ref "C33") (pin "1") (pinfunction "1_1") (pintype "passive"))
      (node (ref "R6") (pin "2") (pinfunction "2_2") (pintype "passive"))
      (node (ref "U11") (pin "7") (pinfunction "VREF2_7") (pintype "bidirectional"))
      (node (ref "U11") (pin "8") (pinfunction "EN_8") (pintype "bidirectional"))
    )
    (net (code "126") (name "PORTA0") (class "Default")
      (node (ref "U$7") (pin "P$1") (pinfunction "P1_P$1") (pintype "bidirectional"))
      (node (ref "U6") (pin "E7") (pinfunction "1_E7") (pintype "bidirectional"))
    )
    (net (code "127") (name "PORTA1") (class "Default")
      (node (ref "U$8") (pin "P$1") (pinfunction "P1_P$1") (pintype "bidirectional"))
      (node (ref "U6") (pin "C8") (pinfunction "1_C8") (pintype "bidirectional"))
    )
    (net (code "128") (name "PORTA2") (class "Default")
      (node (ref "U$7") (pin "P$2") (pinfunction "P2_P$2") (pintype "bidirectional"))
      (node (ref "U6") (pin "D8") (pinfunction "1_D8") (pintype "bidirectional"))
    )
    (net (code "129") (name "PORTA3") (class "Default")
      (node (ref "U$8") (pin "P$2") (pinfunction "P2_P$2") (pintype "bidirectional"))
      (node (ref "U6") (pin "E8") (pinfunction "1_E8") (pintype "bidirectional"))
    )
    (net (code "130") (name "PORTA4") (class "Default")
      (node (ref "U$7") (pin "P$3") (pinfunction "P3_P$3") (pintype "bidirectional"))
      (node (ref "U6") (pin "D9") (pinfunction "1_D9") (pintype "bidirectional"))
    )
    (net (code "131") (name "PORTA5") (class "Default")
      (node (ref "U$8") (pin "P$3") (pinfunction "P3_P$3") (pintype "bidirectional"))
      (node (ref "U6") (pin "A10") (pinfunction "1_A10") (pintype "bidirectional"))
    )
    (net (code "132") (name "PORTA6") (class "Default")
      (node (ref "U$7") (pin "P$5") (pinfunction "P5_P$5") (pintype "bidirectional"))
      (node (ref "U6") (pin "B10") (pinfunction "1_B10") (pintype "bidirectional"))
    )
    (net (code "133") (name "PORTA7") (class "Default")
      (node (ref "U$8") (pin "P$5") (pinfunction "P5_P$5") (pintype "bidirectional"))
      (node (ref "U6") (pin "C10") (pinfunction "1_C10") (pintype "bidirectional"))
    )
    (net (code "134") (name "PORTA8") (class "Default")
      (node (ref "U$7") (pin "P$6") (pinfunction "P6_P$6") (pintype "bidirectional"))
      (node (ref "U6") (pin "E10") (pinfunction "1_E10") (pintype "bidirectional"))
    )
    (net (code "135") (name "PORTA9") (class "Default")
      (node (ref "U$8") (pin "P$6") (pinfunction "P6_P$6") (pintype "bidirectional"))
      (node (ref "U6") (pin "F9") (pinfunction "1_F9") (pintype "bidirectional"))
    )
    (net (code "136") (name "PORTA10") (class "Default")
      (node (ref "U$7") (pin "P$7") (pinfunction "P7_P$7") (pintype "bidirectional"))
      (node (ref "U6") (pin "F10") (pinfunction "1_F10") (pintype "bidirectional"))
    )
    (net (code "137") (name "PORTA11") (class "Default")
      (node (ref "U$8") (pin "P$7") (pinfunction "P7_P$7") (pintype "bidirectional"))
      (node (ref "U6") (pin "D11") (pinfunction "1_D11") (pintype "bidirectional"))
    )
    (net (code "138") (name "PORTB0") (class "Default")
      (node (ref "U$7") (pin "P$9") (pinfunction "P9_P$9") (pintype "bidirectional"))
      (node (ref "U6") (pin "E11") (pinfunction "1_E11") (pintype "bidirectional"))
    )
    (net (code "139") (name "PORTB1") (class "Default")
      (node (ref "U$8") (pin "P$9") (pinfunction "P9_P$9") (pintype "bidirectional"))
      (node (ref "U6") (pin "D14") (pinfunction "1_D14") (pintype "bidirectional"))
    )
    (net (code "140") (name "PORTB2") (class "Default")
      (node (ref "U$7") (pin "P$10") (pinfunction "P10_P$10") (pintype "bidirectional"))
      (node (ref "U6") (pin "D12") (pinfunction "1_D12") (pintype "bidirectional"))
    )
    (net (code "141") (name "PORTB3") (class "Default")
      (node (ref "U$8") (pin "P$10") (pinfunction "P10_P$10") (pintype "bidirectional"))
      (node (ref "U6") (pin "E12") (pinfunction "1_E12") (pintype "bidirectional"))
    )
    (net (code "142") (name "PORTB4") (class "Default")
      (node (ref "U$7") (pin "P$11") (pinfunction "P11_P$11") (pintype "bidirectional"))
      (node (ref "U6") (pin "E13") (pinfunction "1_E13") (pintype "bidirectional"))
    )
    (net (code "143") (name "PORTB5") (class "Default")
      (node (ref "U$8") (pin "P$11") (pinfunction "P11_P$11") (pintype "bidirectional"))
      (node (ref "U6") (pin "F13") (pinfunction "1_F13") (pintype "bidirectional"))
    )
    (net (code "144") (name "PORTB6") (class "Default")
      (node (ref "U$7") (pin "P$13") (pinfunction "P13_P$13") (pintype "bidirectional"))
      (node (ref "U6") (pin "F12") (pinfunction "1_F12") (pintype "bidirectional"))
    )
    (net (code "145") (name "PORTB7") (class "Default")
      (node (ref "U$8") (pin "P$13") (pinfunction "P13_P$13") (pintype "bidirectional"))
      (node (ref "U6") (pin "F14") (pinfunction "1_F14") (pintype "bidirectional"))
    )
    (net (code "146") (name "PORTB8") (class "Default")
      (node (ref "U$7") (pin "P$14") (pinfunction "P14_P$14") (pintype "bidirectional"))
      (node (ref "U6") (pin "G12") (pinfunction "1_G12") (pintype "bidirectional"))
    )
    (net (code "147") (name "PORTB9") (class "Default")
      (node (ref "U$8") (pin "P$14") (pinfunction "P14_P$14") (pintype "bidirectional"))
      (node (ref "U6") (pin "G14") (pinfunction "1_G14") (pintype "bidirectional"))
    )
    (net (code "148") (name "PORTB10") (class "Default")
      (node (ref "U$7") (pin "P$15") (pinfunction "P15_P$15") (pintype "bidirectional"))
      (node (ref "U6") (pin "H14") (pinfunction "1_H14") (pintype "bidirectional"))
    )
    (net (code "149") (name "PORTB11") (class "Default")
      (node (ref "U$8") (pin "P$15") (pinfunction "P15_P$15") (pintype "bidirectional"))
      (node (ref "U6") (pin "J14") (pinfunction "1_J14") (pintype "bidirectional"))
    )
    (net (code "150") (name "PORTC0") (class "Default")
      (node (ref "U$7") (pin "P$17") (pinfunction "P17_P$17") (pintype "bidirectional"))
      (node (ref "U6") (pin "J13") (pinfunction "1_J13") (pintype "bidirectional"))
    )
    (net (code "151") (name "PORTC1") (class "Default")
      (node (ref "U$8") (pin "P$17") (pinfunction "P17_P$17") (pintype "bidirectional"))
      (node (ref "U6") (pin "J12") (pinfunction "1_J12") (pintype "bidirectional"))
    )
    (net (code "152") (name "PORTC2") (class "Default")
      (node (ref "U$7") (pin "P$18") (pinfunction "P18_P$18") (pintype "bidirectional"))
      (node (ref "U6") (pin "K14") (pinfunction "1_K14") (pintype "bidirectional"))
    )
    (net (code "153") (name "PORTC3") (class "Default")
      (node (ref "U$8") (pin "P$18") (pinfunction "P18_P$18") (pintype "bidirectional"))
      (node (ref "U6") (pin "L14") (pinfunction "1_L14") (pintype "bidirectional"))
    )
    (net (code "154") (name "PORTC4") (class "Default")
      (node (ref "U$7") (pin "P$19") (pinfunction "P19_P$19") (pintype "bidirectional"))
      (node (ref "U6") (pin "L13") (pinfunction "1_L13") (pintype "bidirectional"))
    )
    (net (code "155") (name "PORTC5") (class "Default")
      (node (ref "U$8") (pin "P$19") (pinfunction "P19_P$19") (pintype "bidirectional"))
      (node (ref "U6") (pin "M14") (pinfunction "1_M14") (pintype "bidirectional"))
    )
    (net (code "156") (name "PORTC6") (class "Default")
      (node (ref "U$7") (pin "P$21") (pinfunction "P21_P$21") (pintype "bidirectional"))
      (node (ref "U6") (pin "M13") (pinfunction "1_M13") (pintype "bidirectional"))
    )
    (net (code "157") (name "PORTC7") (class "Default")
      (node (ref "U$8") (pin "P$21") (pinfunction "P21_P$21") (pintype "bidirectional"))
      (node (ref "U6") (pin "N14") (pinfunction "1_N14") (pintype "bidirectional"))
    )
    (net (code "158") (name "PORTC8") (class "Default")
      (node (ref "U$7") (pin "P$22") (pinfunction "P22_P$22") (pintype "bidirectional"))
      (node (ref "U6") (pin "M12") (pinfunction "1_M12") (pintype "bidirectional"))
    )
    (net (code "159") (name "PORTC9") (class "Default")
      (node (ref "U$8") (pin "P$22") (pinfunction "P22_P$22") (pintype "bidirectional"))
      (node (ref "U6") (pin "N12") (pinfunction "1_N12") (pintype "bidirectional"))
    )
    (net (code "160") (name "PORTC10") (class "Default")
      (node (ref "U$7") (pin "P$23") (pinfunction "P23_P$23") (pintype "bidirectional"))
      (node (ref "U6") (pin "P12") (pinfunction "1_P12") (pintype "bidirectional"))
    )
    (net (code "161") (name "PORTC11") (class "Default")
      (node (ref "U$8") (pin "P$23") (pinfunction "P23_P$23") (pintype "bidirectional"))
      (node (ref "U6") (pin "M11") (pinfunction "1_M11") (pintype "bidirectional"))
    )
    (net (code "162") (name "PORTD0") (class "Default")
      (node (ref "J4") (pin "P$7") (pinfunction "P7_P$7") (pintype "bidirectional"))
      (node (ref "U6") (pin "D6") (pinfunction "1_D6") (pintype "bidirectional"))
    )
    (net (code "163") (name "PORTD1") (class "Default")
      (node (ref "J6") (pin "P$7") (pinfunction "P7_P$7") (pintype "bidirectional"))
      (node (ref "U6") (pin "C6") (pinfunction "1_C6") (pintype "bidirectional"))
    )
    (net (code "164") (name "PORTD2") (class "Default")
      (node (ref "J4") (pin "P$8") (pinfunction "P8_P$8") (pintype "bidirectional"))
      (node (ref "U6") (pin "E6") (pinfunction "1_E6") (pintype "bidirectional"))
    )
    (net (code "165") (name "PORTD3") (class "Default")
      (node (ref "J6") (pin "P$8") (pinfunction "P8_P$8") (pintype "bidirectional"))
      (node (ref "U6") (pin "C5") (pinfunction "1_C5") (pintype "bidirectional"))
    )
    (net (code "166") (name "PORTE0") (class "Default")
      (node (ref "J4") (pin "P$10") (pinfunction "P10_P$10") (pintype "bidirectional"))
      (node (ref "U6") (pin "D5") (pinfunction "1_D5") (pintype "bidirectional"))
    )
    (net (code "167") (name "PORTE1") (class "Default")
      (node (ref "J6") (pin "P$10") (pinfunction "P10_P$10") (pintype "bidirectional"))
      (node (ref "U6") (pin "A4") (pinfunction "1_A4") (pintype "bidirectional"))
    )
    (net (code "168") (name "PORTE2") (class "Default")
      (node (ref "J4") (pin "P$11") (pinfunction "P11_P$11") (pintype "bidirectional"))
      (node (ref "U6") (pin "G5") (pinfunction "1_G5") (pintype "bidirectional"))
    )
    (net (code "169") (name "PORTE3") (class "Default")
      (node (ref "J6") (pin "P$11") (pinfunction "P11_P$11") (pintype "bidirectional"))
      (node (ref "U6") (pin "A3") (pinfunction "1_A3") (pintype "bidirectional"))
    )
    (net (code "170") (name "PORTE4") (class "Default")
      (node (ref "J4") (pin "P$12") (pinfunction "P12_P$12") (pintype "bidirectional"))
      (node (ref "U6") (pin "B3") (pinfunction "1_B3") (pintype "bidirectional"))
    )
    (net (code "171") (name "PORTE5") (class "Default")
      (node (ref "J6") (pin "P$12") (pinfunction "P12_P$12") (pintype "bidirectional"))
      (node (ref "U6") (pin "A2") (pinfunction "1_A2") (pintype "bidirectional"))
    )
    (net (code "172") (name "PORTE6") (class "Default")
      (node (ref "J4") (pin "P$14") (pinfunction "P14_P$14") (pintype "bidirectional"))
      (node (ref "U6") (pin "B2") (pinfunction "1_B2") (pintype "bidirectional"))
    )
    (net (code "173") (name "PORTE7") (class "Default")
      (node (ref "J6") (pin "P$14") (pinfunction "P14_P$14") (pintype "bidirectional"))
      (node (ref "U6") (pin "C3") (pinfunction "1_C3") (pintype "bidirectional"))
    )
    (net (code "174") (name "PORTE8") (class "Default")
      (node (ref "J4") (pin "P$15") (pinfunction "P15_P$15") (pintype "bidirectional"))
      (node (ref "U6") (pin "C2") (pinfunction "1_C2") (pintype "bidirectional"))
    )
    (net (code "175") (name "PORTE9") (class "Default")
      (node (ref "J6") (pin "P$15") (pinfunction "P15_P$15") (pintype "bidirectional"))
      (node (ref "U6") (pin "D3") (pinfunction "1_D3") (pintype "bidirectional"))
    )
    (net (code "176") (name "PORTE10") (class "Default")
      (node (ref "J4") (pin "P$16") (pinfunction "P16_P$16") (pintype "bidirectional"))
      (node (ref "U6") (pin "D1") (pinfunction "1_D1") (pintype "bidirectional"))
    )
    (net (code "177") (name "PORTE11") (class "Default")
      (node (ref "J6") (pin "P$16") (pinfunction "P16_P$16") (pintype "bidirectional"))
      (node (ref "U6") (pin "E3") (pinfunction "1_E3") (pintype "bidirectional"))
    )
    (net (code "178") (name "PORTF0") (class "Default")
      (node (ref "J4") (pin "P$18") (pinfunction "P18_P$18") (pintype "bidirectional"))
      (node (ref "U6") (pin "E2") (pinfunction "1_E2") (pintype "bidirectional"))
    )
    (net (code "179") (name "PORTF1") (class "Default")
      (node (ref "J6") (pin "P$18") (pinfunction "P18_P$18") (pintype "bidirectional"))
      (node (ref "U6") (pin "E1") (pinfunction "1_E1") (pintype "bidirectional"))
    )
    (net (code "180") (name "PORTF2") (class "Default")
      (node (ref "J4") (pin "P$19") (pinfunction "P19_P$19") (pintype "bidirectional"))
      (node (ref "U6") (pin "E4") (pinfunction "1_E4") (pintype "bidirectional"))
    )
    (net (code "181") (name "PORTF3") (class "Default")
      (node (ref "J6") (pin "P$19") (pinfunction "P19_P$19") (pintype "bidirectional"))
      (node (ref "U6") (pin "F4") (pinfunction "1_F4") (pintype "bidirectional"))
    )
    (net (code "182") (name "PORTF4") (class "Default")
      (node (ref "J4") (pin "P$20") (pinfunction "P20_P$20") (pintype "bidirectional"))
      (node (ref "U6") (pin "F5") (pinfunction "1_F5") (pintype "bidirectional"))
    )
    (net (code "183") (name "PORTF5") (class "Default")
      (node (ref "J6") (pin "P$20") (pinfunction "P20_P$20") (pintype "bidirectional"))
      (node (ref "U6") (pin "G3") (pinfunction "1_G3") (pintype "bidirectional"))
    )
    (net (code "184") (name "PORTF6") (class "Default")
      (node (ref "J4") (pin "P$22") (pinfunction "P22_P$22") (pintype "bidirectional"))
      (node (ref "U6") (pin "F3") (pinfunction "1_F3") (pintype "bidirectional"))
    )
    (net (code "185") (name "PORTF7") (class "Default")
      (node (ref "J6") (pin "P$22") (pinfunction "P22_P$22") (pintype "bidirectional"))
      (node (ref "U6") (pin "G1") (pinfunction "1_G1") (pintype "bidirectional"))
    )
    (net (code "186") (name "PORTF8") (class "Default")
      (node (ref "J4") (pin "P$23") (pinfunction "P23_P$23") (pintype "bidirectional"))
      (node (ref "U6") (pin "H3") (pinfunction "1_H3") (pintype "bidirectional"))
    )
    (net (code "187") (name "PORTF9") (class "Default")
      (node (ref "J6") (pin "P$23") (pinfunction "P23_P$23") (pintype "bidirectional"))
      (node (ref "U6") (pin "H1") (pinfunction "1_H1") (pintype "bidirectional"))
    )
    (net (code "188") (name "PORTF10") (class "Default")
      (node (ref "J4") (pin "P$24") (pinfunction "P24_P$24") (pintype "bidirectional"))
      (node (ref "U6") (pin "H2") (pinfunction "1_H2") (pintype "bidirectional"))
    )
    (net (code "189") (name "PORTF11") (class "Default")
      (node (ref "J6") (pin "P$24") (pinfunction "P24_P$24") (pintype "bidirectional"))
      (node (ref "U6") (pin "J1") (pinfunction "1_J1") (pintype "bidirectional"))
    )
    (net (code "190") (name "RAS#") (class "Default")
      (node (ref "U6") (pin "R2") (pinfunction "1_R2") (pintype "bidirectional"))
      (node (ref "U9") (pin "18") (pinfunction "P$1_18") (pintype "bidirectional"))
    )
    (net (code "191") (name "REBOOT") (class "Default")
      (node (ref "R18") (pin "1") (pinfunction "1_1") (pintype "passive"))
      (node (ref "S1") (pin "3") (pinfunction "3_3") (pintype "passive"))
      (node (ref "S1") (pin "4") (pinfunction "4_4") (pintype "passive"))
      (node (ref "U6") (pin "T2") (pinfunction "1_T2") (pintype "input"))
    )
    (net (code "192") (name "SDRAM-CLK") (class "Default")
      (node (ref "U6") (pin "G16") (pinfunction "1_G16") (pintype "bidirectional"))
      (node (ref "U9") (pin "38") (pinfunction "P$1_38") (pintype "bidirectional"))
    )
    (net (code "193") (name "SDRAM-CS#") (class "Default")
      (node (ref "U6") (pin "R1") (pinfunction "1_R1") (pintype "bidirectional"))
      (node (ref "U9") (pin "19") (pinfunction "P$1_19") (pintype "bidirectional"))
    )
    (net (code "194") (name "SD_CD{slash}DAT3") (class "Default")
      (node (ref "J5") (pin "T2") (pinfunction "CD/DAT3_T2") (pintype "bidirectional"))
      (node (ref "U6") (pin "K12") (pinfunction "1_K12") (pintype "bidirectional"))
    )
    (net (code "195") (name "SD_CLK") (class "Default")
      (node (ref "J5") (pin "T5") (pinfunction "CLK_T5") (pintype "bidirectional"))
      (node (ref "U6") (pin "L12") (pinfunction "1_L12") (pintype "bidirectional"))
    )
    (net (code "196") (name "SD_CMD") (class "Default")
      (node (ref "J5") (pin "T3") (pinfunction "CMD_T3") (pintype "bidirectional"))
      (node (ref "U6") (pin "K11") (pinfunction "1_K11") (pintype "bidirectional"))
    )
    (net (code "197") (name "SD_DAT0") (class "Default")
      (node (ref "J5") (pin "T7") (pinfunction "DAT0_T7") (pintype "bidirectional"))
      (node (ref "U6") (pin "M10") (pinfunction "1_M10") (pintype "bidirectional"))
    )
    (net (code "198") (name "SD_DAT1") (class "Default")
      (node (ref "J5") (pin "T8") (pinfunction "DAT1_T8") (pintype "bidirectional"))
      (node (ref "U6") (pin "L10") (pinfunction "1_L10") (pintype "bidirectional"))
    )
    (net (code "199") (name "SD_DAT2") (class "Default")
      (node (ref "J5") (pin "T1") (pinfunction "DAT2_T1") (pintype "bidirectional"))
      (node (ref "U6") (pin "J11") (pinfunction "1_J11") (pintype "bidirectional"))
    )
    (net (code "200") (name "SW1") (class "Default")
      (node (ref "S2") (pin "8") (pinfunction "8_8") (pintype "passive"))
      (node (ref "U6") (pin "L1") (pinfunction "1_L1") (pintype "bidirectional"))
    )
    (net (code "201") (name "SW2") (class "Default")
      (node (ref "S2") (pin "7") (pinfunction "7_7") (pintype "passive"))
      (node (ref "U6") (pin "L3") (pinfunction "1_L3") (pintype "bidirectional"))
    )
    (net (code "202") (name "SW3") (class "Default")
      (node (ref "S2") (pin "6") (pinfunction "6_6") (pintype "passive"))
      (node (ref "U6") (pin "L4") (pinfunction "1_L4") (pintype "bidirectional"))
    )
    (net (code "203") (name "SW4") (class "Default")
      (node (ref "S2") (pin "5") (pinfunction "5_5") (pintype "passive"))
      (node (ref "U6") (pin "L5") (pinfunction "1_L5") (pintype "bidirectional"))
    )
    (net (code "204") (name "TCK") (class "Default")
      (node (ref "U2") (pin "16") (pinfunction "ADBUS0/TXD/TCK/SK_16") (pintype "bidirectional"))
      (node (ref "U6") (pin "C14") (pinfunction "1_C14") (pintype "input"))
    )
    (net (code "205") (name "TDI") (class "Default")
      (node (ref "U2") (pin "17") (pinfunction "ADBUS1/RXD/TDI/DO_17") (pintype "bidirectional"))
      (node (ref "U6") (pin "C12") (pinfunction "1_C12") (pintype "input"))
    )
    (net (code "206") (name "TDO") (class "Default")
      (node (ref "U2") (pin "18") (pinfunction "ADBUS2/RTS#/TDO/DI_18") (pintype "bidirectional"))
      (node (ref "U6") (pin "E14") (pinfunction "1_E14") (pintype "output"))
    )
    (net (code "207") (name "TMDS0_N") (class "Default")
      (node (ref "J2") (pin "9") (pinfunction "DATA0-_9") (pintype "bidirectional"))
      (node (ref "RN8") (pin "4") (pinfunction "2_4") (pintype "passive"))
      (node (ref "U6") (pin "A7") (pinfunction "1_A7") (pintype "bidirectional"))
    )
    (net (code "208") (name "TMDS0_P") (class "Default")
      (node (ref "J2") (pin "7") (pinfunction "DATA0+_7") (pintype "bidirectional"))
      (node (ref "RN8") (pin "2") (pinfunction "1_2") (pintype "passive"))
      (node (ref "U6") (pin "C7") (pinfunction "1_C7") (pintype "bidirectional"))
    )
    (net (code "209") (name "TMDS1_N") (class "Default")
      (node (ref "J2") (pin "6") (pinfunction "DATA1-_6") (pintype "bidirectional"))
      (node (ref "RN3") (pin "4") (pinfunction "2_4") (pintype "passive"))
      (node (ref "U6") (pin "A6") (pinfunction "1_A6") (pintype "bidirectional"))
    )
    (net (code "210") (name "TMDS1_P") (class "Default")
      (node (ref "J2") (pin "4") (pinfunction "DATA1+_4") (pintype "bidirectional"))
      (node (ref "RN3") (pin "2") (pinfunction "1_2") (pintype "passive"))
      (node (ref "U6") (pin "B6") (pinfunction "1_B6") (pintype "bidirectional"))
    )
    (net (code "211") (name "TMDS2_N") (class "Default")
      (node (ref "J2") (pin "3") (pinfunction "DATA2-_3") (pintype "bidirectional"))
      (node (ref "RN4") (pin "4") (pinfunction "2_4") (pintype "passive"))
      (node (ref "U6") (pin "A5") (pinfunction "1_A5") (pintype "bidirectional"))
    )
    (net (code "212") (name "TMDS2_P") (class "Default")
      (node (ref "J2") (pin "1") (pinfunction "DATA2+_1") (pintype "bidirectional"))
      (node (ref "RN4") (pin "2") (pinfunction "1_2") (pintype "passive"))
      (node (ref "U6") (pin "B5") (pinfunction "1_B5") (pintype "bidirectional"))
    )
    (net (code "213") (name "TMDS_CLK_N") (class "Default")
      (node (ref "J2") (pin "12") (pinfunction "CLOCK-_12") (pintype "bidirectional"))
      (node (ref "RN9") (pin "4") (pinfunction "2_4") (pintype "passive"))
      (node (ref "U6") (pin "A9") (pinfunction "1_A9") (pintype "bidirectional"))
    )
    (net (code "214") (name "TMDS_CLK_P") (class "Default")
      (node (ref "J2") (pin "10") (pinfunction "CLOCK+_10") (pintype "bidirectional"))
      (node (ref "RN9") (pin "2") (pinfunction "1_2") (pintype "passive"))
      (node (ref "U6") (pin "C9") (pinfunction "1_C9") (pintype "bidirectional"))
    )
    (net (code "215") (name "TMS") (class "Default")
      (node (ref "U2") (pin "19") (pinfunction "ADBUS3/CTS#/TMS/CS_19") (pintype "bidirectional"))
      (node (ref "U6") (pin "A15") (pinfunction "1_A15") (pintype "input"))
    )
    (net (code "216") (name "TX_HDMI_5V") (class "Default")
      (node (ref "J2") (pin "18") (pinfunction "+5V_18") (pintype "bidirectional"))
      (node (ref "R14") (pin "1") (pinfunction "1_1") (pintype "passive"))
      (node (ref "R6") (pin "1") (pinfunction "1_1") (pintype "passive"))
      (node (ref "RN5") (pin "3") (pinfunction "1_3") (pintype "passive"))
      (node (ref "RN5") (pin "4") (pinfunction "1_4") (pintype "passive"))
    )
    (net (code "217") (name "UDQM") (class "Default")
      (node (ref "U6") (pin "F15") (pinfunction "1_F15") (pintype "bidirectional"))
      (node (ref "U9") (pin "39") (pinfunction "P$1_39") (pintype "bidirectional"))
    )
    (net (code "218") (name "VCORE") (class "Default")
      (node (ref "C2") (pin "1") (pinfunction "1_1") (pintype "passive"))
      (node (ref "C4") (pin "1") (pinfunction "1_1") (pintype "passive"))
      (node (ref "C7") (pin "1") (pinfunction "1_1") (pintype "passive"))
      (node (ref "C9") (pin "1") (pinfunction "1_1") (pintype "passive"))
      (node (ref "U2") (pin "12") (pinfunction "VCORE0_12") (pintype "bidirectional"))
      (node (ref "U2") (pin "37") (pinfunction "VCORE1_37") (pintype "bidirectional"))
      (node (ref "U2") (pin "49") (pinfunction "VREGOUT_49") (pintype "bidirectional"))
      (node (ref "U2") (pin "64") (pinfunction "VCORE2_64") (pintype "bidirectional"))
    )
    (net (code "219") (name "WE#") (class "Default")
      (node (ref "U6") (pin "R5") (pinfunction "1_R5") (pintype "bidirectional"))
      (node (ref "U9") (pin "16") (pinfunction "P$1_16") (pintype "bidirectional"))
    )
    (net (code "220") (name "unconnected-(J2-CEC-Pad13)") (class "Default")
      (node (ref "J2") (pin "13") (pinfunction "CEC_13") (pintype "bidirectional"))
    )
    (net (code "221") (name "unconnected-(J3-+5V-Pad18)") (class "Default")
      (node (ref "J3") (pin "18") (pinfunction "+5V_18") (pintype "bidirectional"))
    )
    (net (code "222") (name "unconnected-(J3-CEC-Pad13)") (class "Default")
      (node (ref "J3") (pin "13") (pinfunction "CEC_13") (pintype "bidirectional"))
    )
    (net (code "223") (name "unconnected-(J3-SCL-Pad15)") (class "Default")
      (node (ref "J3") (pin "15") (pinfunction "SCL_15") (pintype "bidirectional"))
    )
    (net (code "224") (name "unconnected-(J3-SDA-Pad16)") (class "Default")
      (node (ref "J3") (pin "16") (pinfunction "SDA_16") (pintype "bidirectional"))
    )
    (net (code "225") (name "unconnected-(J5-PadS1)") (class "Default")
      (node (ref "J5") (pin "S1") (pinfunction "S1_S1") (pintype "bidirectional"))
    )
    (net (code "226") (name "unconnected-(J5-PadS2)") (class "Default")
      (node (ref "J5") (pin "S2") (pinfunction "S2_S2") (pintype "bidirectional"))
    )
    (net (code "227") (name "unconnected-(JP5-PadRING2)") (class "Default")
      (node (ref "JP5") (pin "RING2") (pinfunction "RING2_RING2") (pintype "bidirectional"))
    )
    (net (code "228") (name "unconnected-(U2-ACBUS0{slash}TXDEN{slash}GPIOH0-Pad26)") (class "Default")
      (node (ref "U2") (pin "26") (pinfunction "ACBUS0/TXDEN/GPIOH0_26") (pintype "bidirectional"))
    )
    (net (code "229") (name "unconnected-(U2-ACBUS1{slash}GPIOH1-Pad27)") (class "Default")
      (node (ref "U2") (pin "27") (pinfunction "ACBUS1/GPIOH1_27") (pintype "bidirectional"))
    )
    (net (code "230") (name "unconnected-(U2-ACBUS2{slash}GPIOH2-Pad28)") (class "Default")
      (node (ref "U2") (pin "28") (pinfunction "ACBUS2/GPIOH2_28") (pintype "bidirectional"))
    )
    (net (code "231") (name "unconnected-(U2-ACBUS3{slash}RXLED#{slash}GPIOH3-Pad29)") (class "Default")
      (node (ref "U2") (pin "29") (pinfunction "ACBUS3/RXLED#/GPIOH3_29") (pintype "bidirectional"))
    )
    (net (code "232") (name "unconnected-(U2-ACBUS4{slash}TXLED#{slash}GPIOH4-Pad30)") (class "Default")
      (node (ref "U2") (pin "30") (pinfunction "ACBUS4/TXLED#/GPIOH4_30") (pintype "bidirectional"))
    )
    (net (code "233") (name "unconnected-(U2-ACBUS5{slash}GPIOH5-Pad32)") (class "Default")
      (node (ref "U2") (pin "32") (pinfunction "ACBUS5/GPIOH5_32") (pintype "bidirectional"))
    )
    (net (code "234") (name "unconnected-(U2-ACBUS6{slash}GPIOH6-Pad33)") (class "Default")
      (node (ref "U2") (pin "33") (pinfunction "ACBUS6/GPIOH6_33") (pintype "bidirectional"))
    )
    (net (code "235") (name "unconnected-(U2-ACBUS7{slash}GPIOH7-Pad34)") (class "Default")
      (node (ref "U2") (pin "34") (pinfunction "ACBUS7/GPIOH7_34") (pintype "bidirectional"))
    )
    (net (code "236") (name "unconnected-(U2-ADBUS4{slash}DTR#{slash}GPIOL0-Pad21)") (class "Default")
      (node (ref "U2") (pin "21") (pinfunction "ADBUS4/DTR#/GPIOL0_21") (pintype "bidirectional"))
    )
    (net (code "237") (name "unconnected-(U2-ADBUS5{slash}DSR#{slash}GPIOL1-Pad22)") (class "Default")
      (node (ref "U2") (pin "22") (pinfunction "ADBUS5/DSR#/GPIOL1_22") (pintype "bidirectional"))
    )
    (net (code "238") (name "unconnected-(U2-ADBUS6{slash}DCD#{slash}GPIOL2-Pad23)") (class "Default")
      (node (ref "U2") (pin "23") (pinfunction "ADBUS6/DCD#/GPIOL2_23") (pintype "bidirectional"))
    )
    (net (code "239") (name "unconnected-(U2-ADBUS7{slash}RI#{slash}GPIOL3-Pad24)") (class "Default")
      (node (ref "U2") (pin "24") (pinfunction "ADBUS7/RI#/GPIOL3_24") (pintype "bidirectional"))
    )
    (net (code "240") (name "unconnected-(U2-BCBUS5{slash}GPIOH5-Pad57)") (class "Default")
      (node (ref "U2") (pin "57") (pinfunction "BCBUS5/GPIOH5_57") (pintype "bidirectional"))
    )
    (net (code "241") (name "unconnected-(U2-BCBUS6{slash}GPIOH6-Pad58)") (class "Default")
      (node (ref "U2") (pin "58") (pinfunction "BCBUS6/GPIOH6_58") (pintype "bidirectional"))
    )
    (net (code "242") (name "unconnected-(U2-BCBUS7{slash}GPIOH7-Pad59)") (class "Default")
      (node (ref "U2") (pin "59") (pinfunction "BCBUS7/GPIOH7_59") (pintype "bidirectional"))
    )
    (net (code "243") (name "unconnected-(U2-PWREN#-Pad60)") (class "Default")
      (node (ref "U2") (pin "60") (pinfunction "PWREN#_60") (pintype "bidirectional"))
    )
    (net (code "244") (name "unconnected-(U2-SUSPEND#-Pad36)") (class "Default")
      (node (ref "U2") (pin "36") (pinfunction "SUSPEND#_36") (pintype "bidirectional"))
    )
    (net (code "245") (name "unconnected-(U6A-1-PadL11)") (class "Default")
      (node (ref "U6") (pin "L11") (pinfunction "1_L11") (pintype "input"))
    )
    (net (code "246") (name "unconnected-(U6AO-1-PadM4)") (class "Default")
      (node (ref "U6") (pin "M4") (pinfunction "1_M4") (pintype "bidirectional"))
    )
    (net (code "247") (name "unconnected-(U6AZ-1-PadN4)") (class "Default")
      (node (ref "U6") (pin "N4") (pinfunction "1_N4") (pintype "bidirectional"))
    )
    (net (code "248") (name "unconnected-(U6BC-1-PadM5)") (class "Default")
      (node (ref "U6") (pin "M5") (pinfunction "1_M5") (pintype "bidirectional"))
    )
    (net (code "249") (name "unconnected-(U6BE-1-PadG11)") (class "Default")
      (node (ref "U6") (pin "G11") (pinfunction "1_G11") (pintype "bidirectional"))
    )
    (net (code "250") (name "unconnected-(U6CS-1-PadK1)") (class "Default")
      (node (ref "U6") (pin "K1") (pinfunction "1_K1") (pintype "bidirectional"))
    )
    (net (code "251") (name "unconnected-(U6CV-1-PadK2)") (class "Default")
      (node (ref "U6") (pin "K2") (pinfunction "1_K2") (pintype "bidirectional"))
    )
    (net (code "252") (name "unconnected-(U6CW-1-PadH11)") (class "Default")
      (node (ref "U6") (pin "H11") (pinfunction "1_H11") (pintype "bidirectional"))
    )
    (net (code "253") (name "unconnected-(U6DB-1-PadJ3)") (class "Default")
      (node (ref "U6") (pin "J3") (pinfunction "1_J3") (pintype "bidirectional"))
    )
    (net (code "254") (name "unconnected-(U6DG-1-PadH13)") (class "Default")
      (node (ref "U6") (pin "H13") (pinfunction "1_H13") (pintype "bidirectional"))
    )
    (net (code "255") (name "unconnected-(U6DS-1-PadF1)") (class "Default")
      (node (ref "U6") (pin "F1") (pinfunction "1_F1") (pintype "bidirectional"))
    )
    (net (code "256") (name "unconnected-(U6DU-1-PadF2)") (class "Default")
      (node (ref "U6") (pin "F2") (pinfunction "1_F2") (pintype "bidirectional"))
    )
    (net (code "257") (name "unconnected-(U6EC-1-PadJ6)") (class "Default")
      (node (ref "U6") (pin "J6") (pinfunction "1_J6") (pintype "bidirectional"))
    )
    (net (code "258") (name "unconnected-(U6ES-1-PadK6)") (class "Default")
      (node (ref "U6") (pin "K6") (pinfunction "1_K6") (pintype "bidirectional"))
    )
    (net (code "259") (name "unconnected-(U6ET-1-PadP6)") (class "Default")
      (node (ref "U6") (pin "P6") (pinfunction "1_P6") (pintype "bidirectional"))
    )
    (net (code "260") (name "unconnected-(U6EV-1-PadK5)") (class "Default")
      (node (ref "U6") (pin "K5") (pinfunction "1_K5") (pintype "bidirectional"))
    )
    (net (code "261") (name "unconnected-(U6GF-1-PadF7)") (class "Default")
      (node (ref "U6") (pin "F7") (pinfunction "1_F7") (pintype "bidirectional"))
    )
    (net (code "262") (name "unconnected-(U6GG-1-PadL7)") (class "Default")
      (node (ref "U6") (pin "L7") (pinfunction "1_L7") (pintype "bidirectional"))
    )
    (net (code "263") (name "unconnected-(U6GJ-1-PadL8)") (class "Default")
      (node (ref "U6") (pin "L8") (pinfunction "1_L8") (pintype "bidirectional"))
    )
    (net (code "264") (name "unconnected-(U9AK-P$1-Pad40)") (class "Default")
      (node (ref "U9") (pin "40") (pinfunction "P$1_40") (pintype "bidirectional"))
    )
    (net (code "265") (name "unconnected-(X1-Pad4)") (class "Default")
      (node (ref "X1") (pin "4") (pinfunction "4_4") (pintype "input"))
    )
  )
)
